# io-board-e-6-renumbered.net
KiCad netlist of a schematic drawn in EAGLE
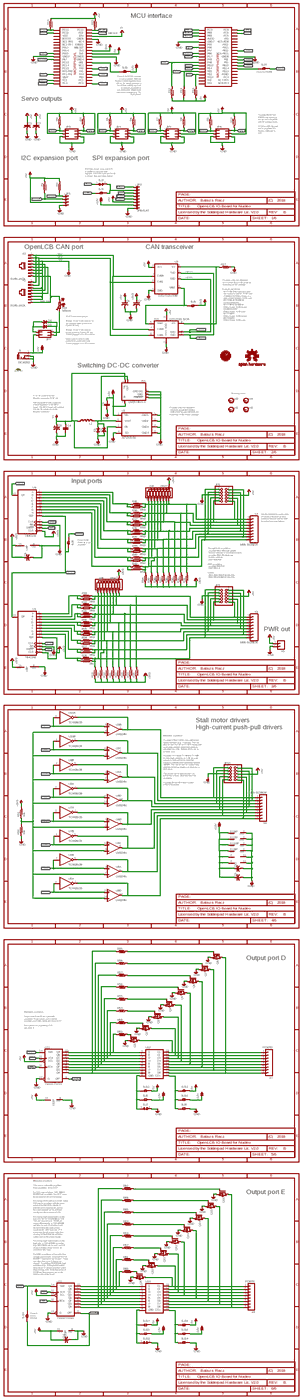
[diagram p0: schematic, sheet 1, overview]
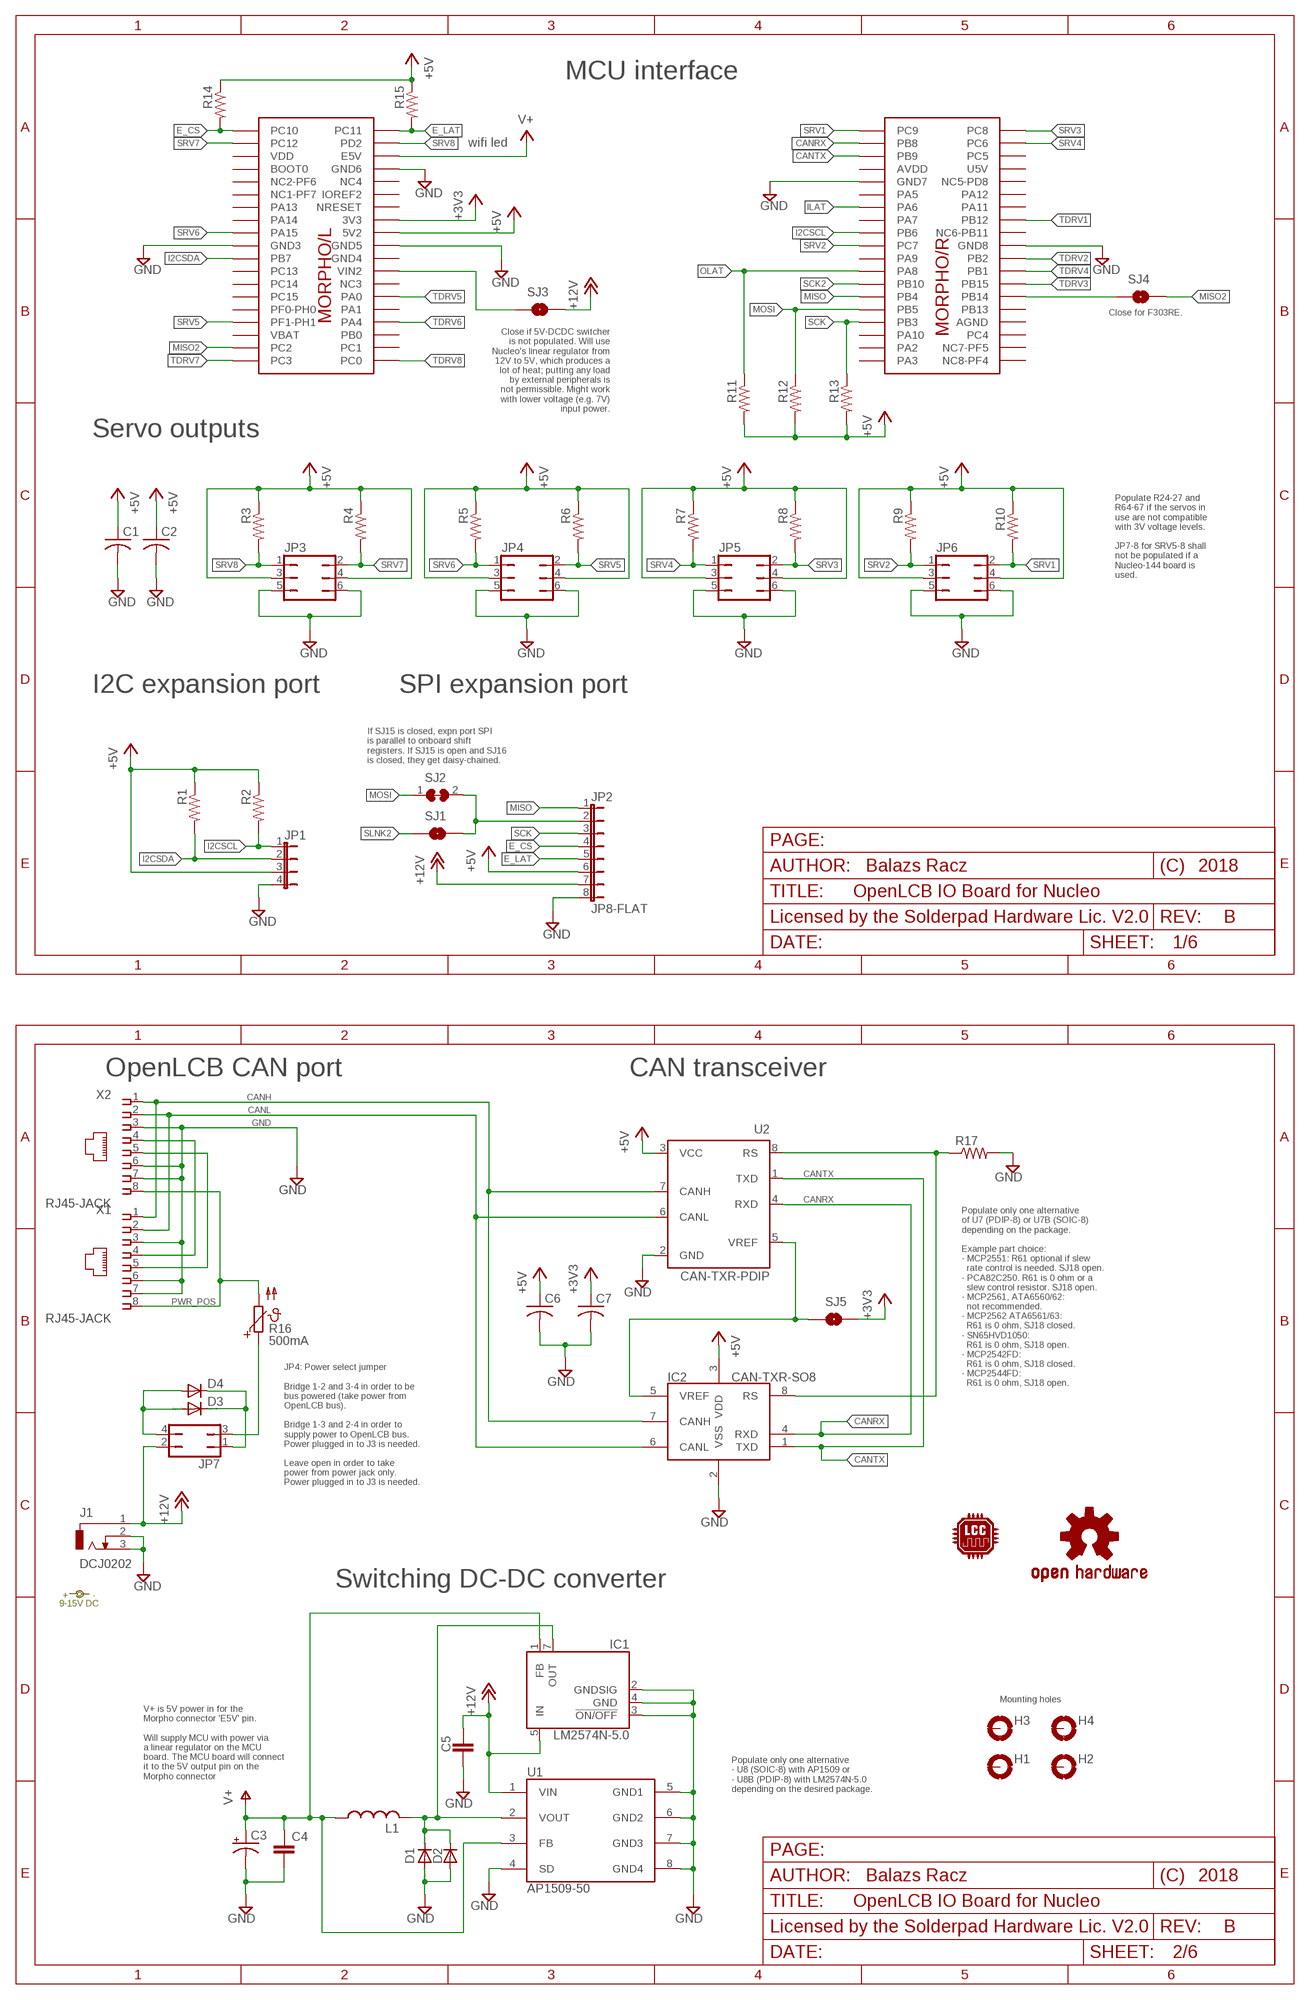
[diagram p1: schematic, sheet 1, part 1 of 4]
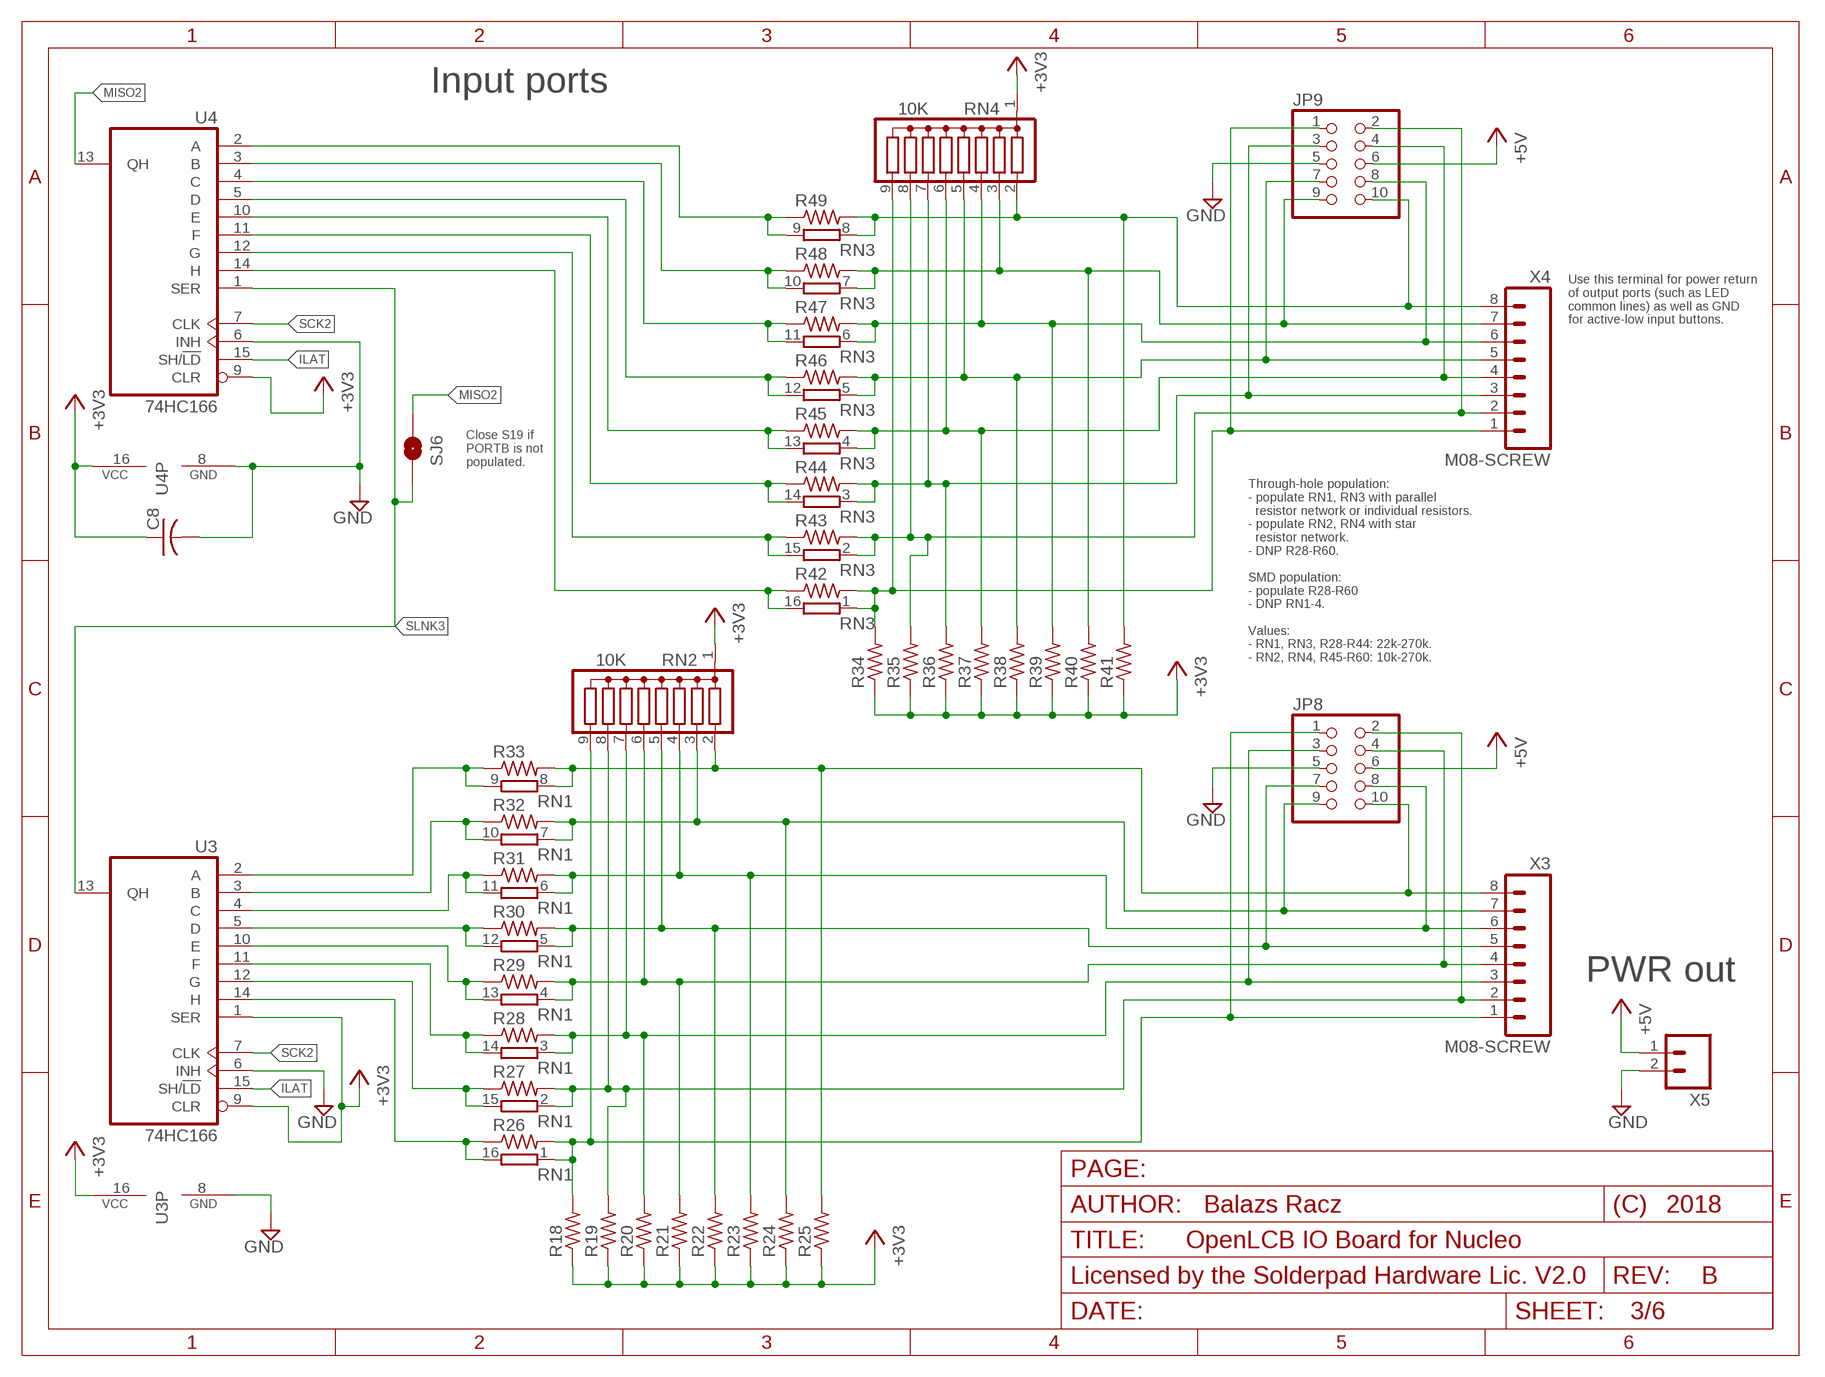
[diagram p2: schematic, sheet 1, part 2 of 4]
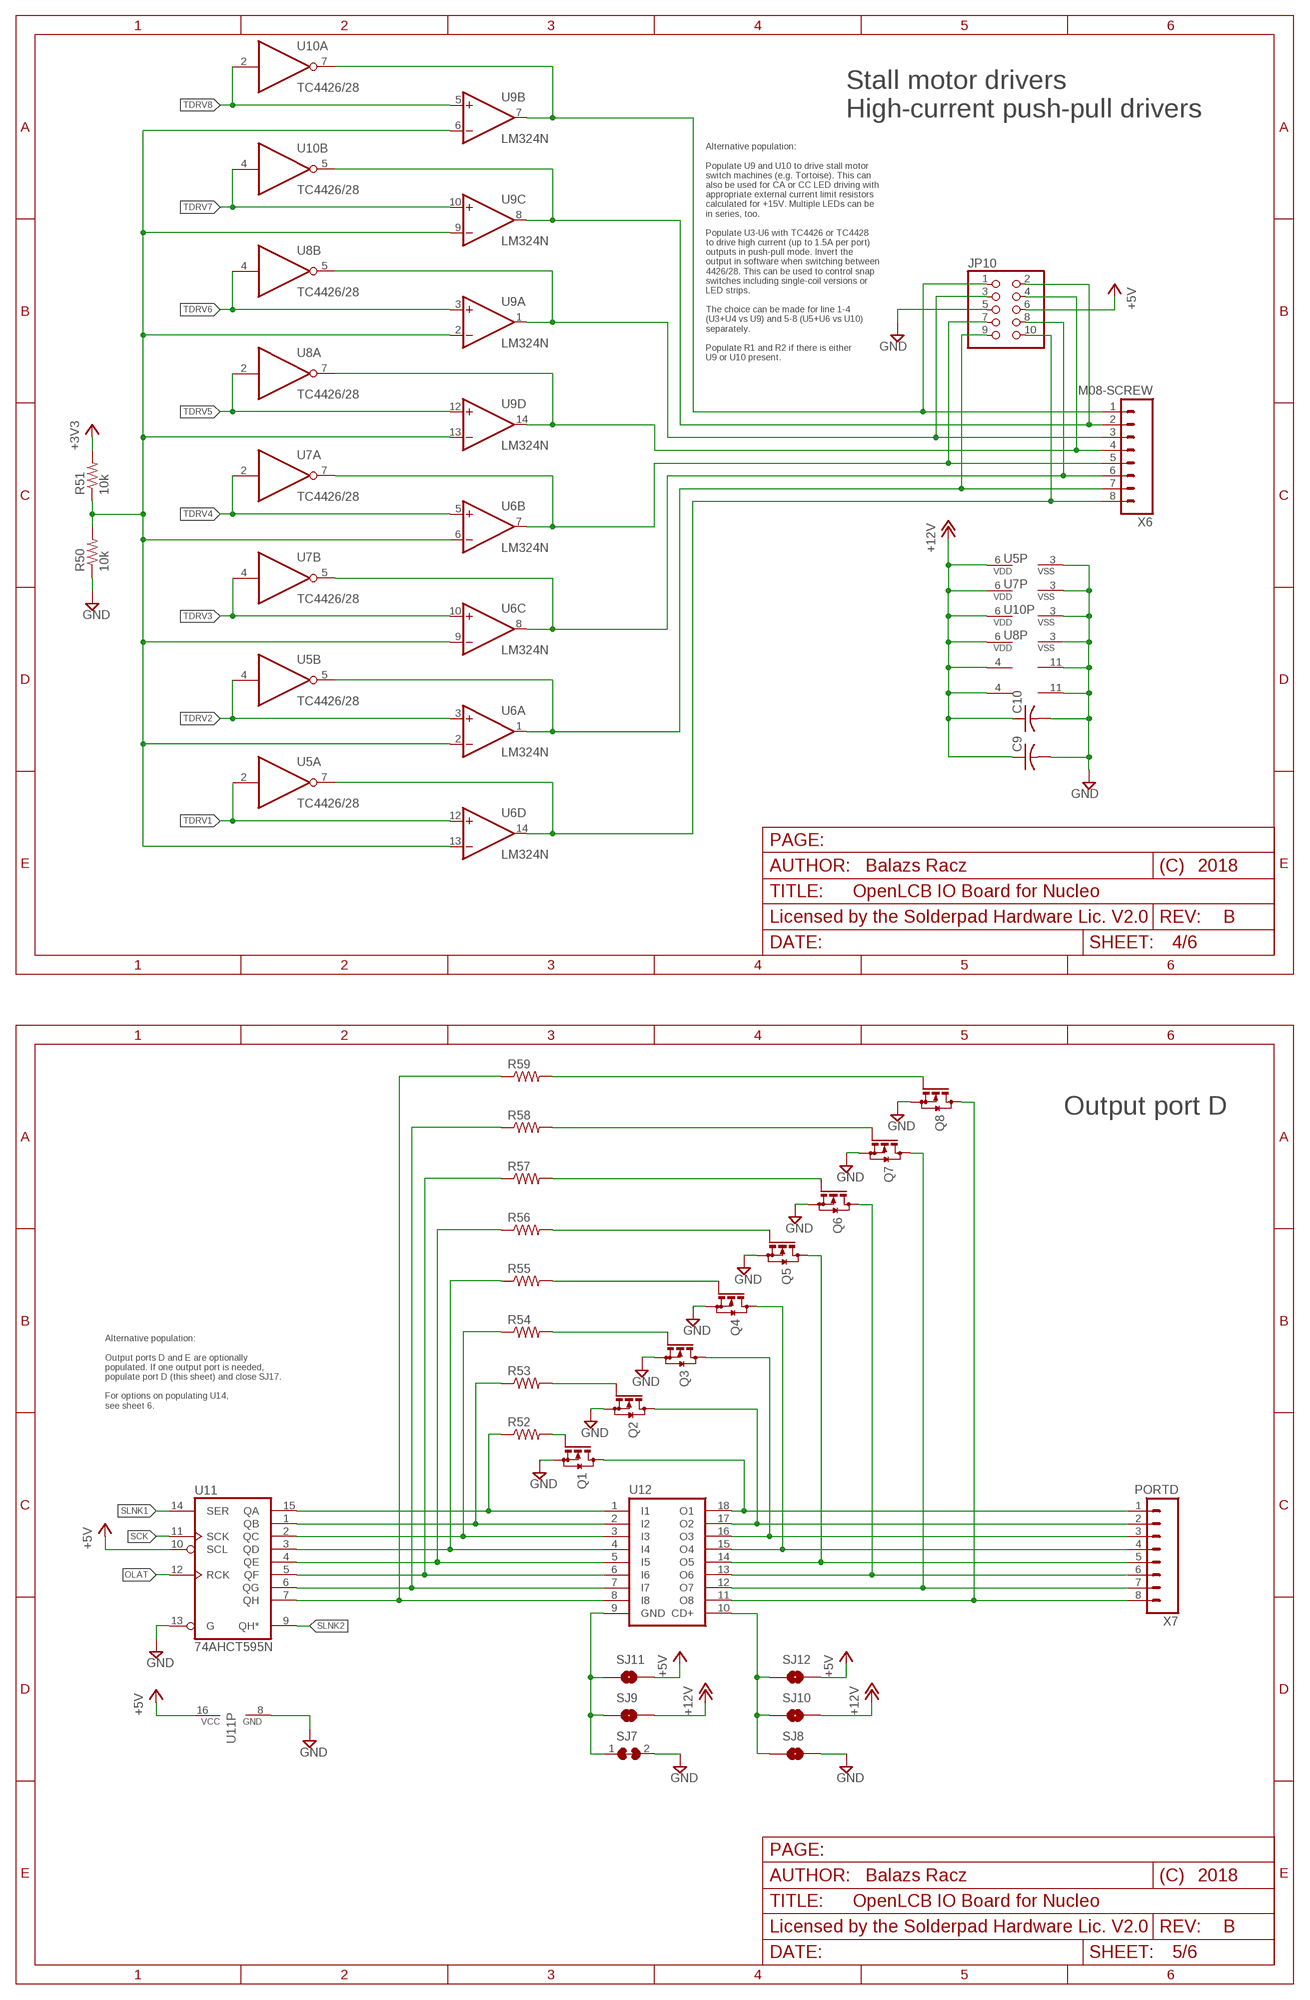
[diagram p3: schematic, sheet 1, part 3 of 4]
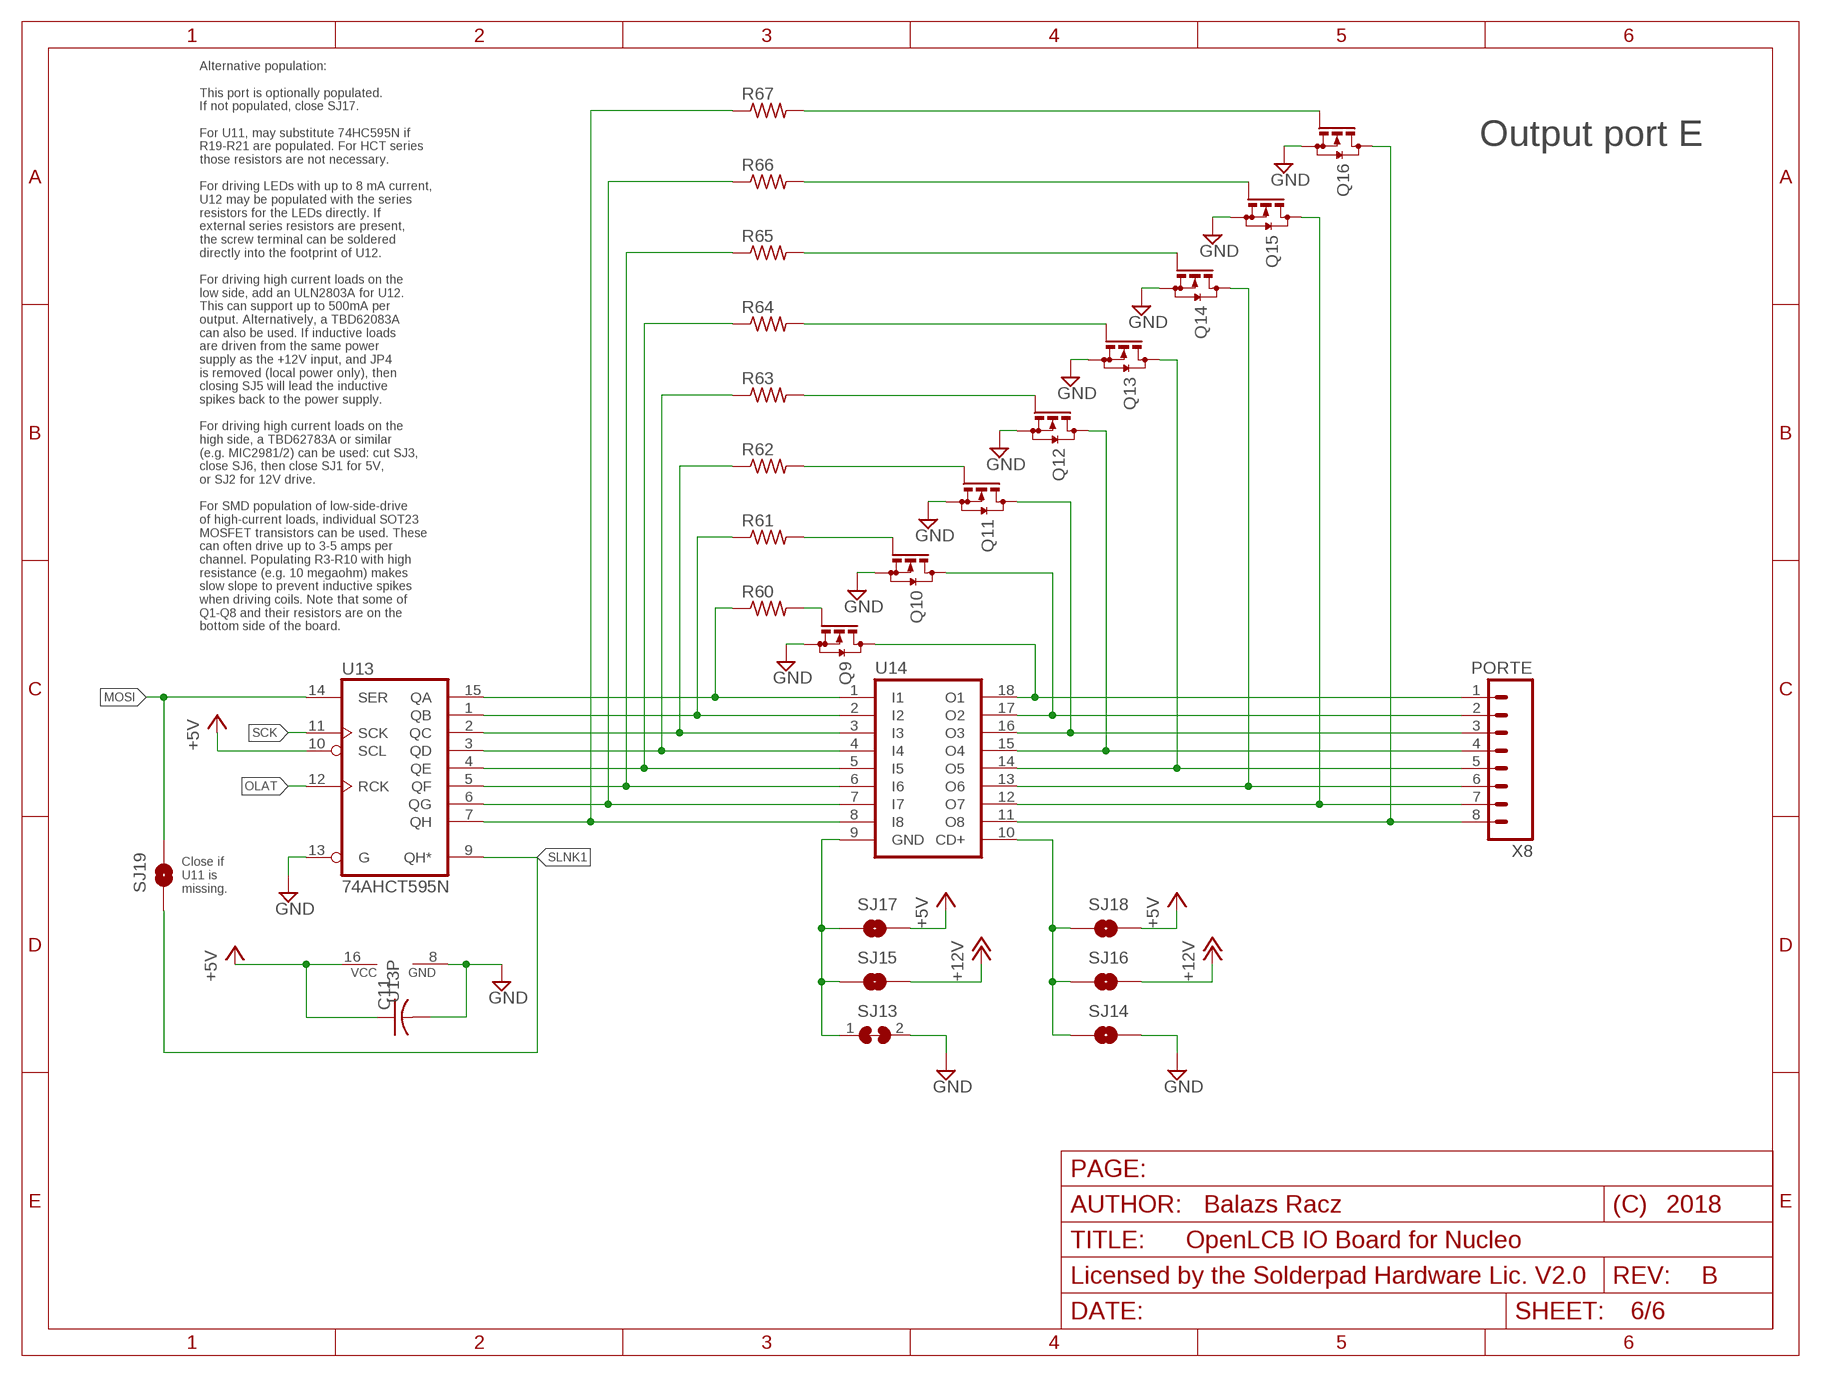
[diagram p4: schematic, sheet 1, part 4 of 4]

(export (version "E")
  (design (tool "Eeschema 10.0.6"))
  (components
    (comp (ref "C1")
      (value "C-USC1206")
      (footprint "eagle-import:C1206")
      (libsource (lib "eagle-import") (part "C-USC1206"))
    )
    (comp (ref "C2")
      (value "C-USC1206")
      (footprint "eagle-import:C1206")
      (libsource (lib "eagle-import") (part "C-USC1206"))
    )
    (comp (ref "C3")
      (value "CPOL-USE2.5-5")
      (footprint "eagle-import:E2,5-5")
      (libsource (lib "eagle-import") (part "CPOL-USE2.5-5"))
    )
    (comp (ref "C4")
      (value "C-EUC1206")
      (footprint "eagle-import:C1206")
      (libsource (lib "eagle-import") (part "C-EUC1206"))
    )
    (comp (ref "C5")
      (value "C-EUC1206")
      (footprint "eagle-import:C1206")
      (libsource (lib "eagle-import") (part "C-EUC1206"))
    )
    (comp (ref "C6")
      (value "C-USC0805")
      (footprint "eagle-import:C0805")
      (libsource (lib "eagle-import") (part "C-USC0805"))
    )
    (comp (ref "C7")
      (value "C-USC0805")
      (footprint "eagle-import:C0805")
      (libsource (lib "eagle-import") (part "C-USC0805"))
    )
    (comp (ref "C8")
      (value "C-USC0805")
      (footprint "eagle-import:C0805")
      (libsource (lib "eagle-import") (part "C-USC0805"))
    )
    (comp (ref "C9")
      (value "C-USC1206")
      (footprint "eagle-import:C1206")
      (libsource (lib "eagle-import") (part "C-USC1206"))
    )
    (comp (ref "C10")
      (value "C-USC1206")
      (footprint "eagle-import:C1206")
      (libsource (lib "eagle-import") (part "C-USC1206"))
    )
    (comp (ref "C11")
      (value "C-USC0805")
      (footprint "eagle-import:C0805")
      (libsource (lib "eagle-import") (part "C-USC0805"))
    )
    (comp (ref "D1")
      (value "DIODE-DO41-7.6")
      (footprint "eagle-import:DO41-7.6")
      (libsource (lib "eagle-import") (part "DIODE-DO41-7.6"))
    )
    (comp (ref "D2")
      (value "DIODEDO-214AA-NODOC")
      (footprint "eagle-import:DO214AA-NODOC")
      (libsource (lib "eagle-import") (part "DIODEDO-214AA-NODOC"))
    )
    (comp (ref "D3")
      (value "DIODE-DO41-7.6")
      (footprint "eagle-import:DO41-7.6")
      (libsource (lib "eagle-import") (part "DIODE-DO41-7.6"))
    )
    (comp (ref "D4")
      (value "DIODEDO-214AA-NODOC")
      (footprint "eagle-import:DO214AA-NODOC")
      (libsource (lib "eagle-import") (part "DIODEDO-214AA-NODOC"))
    )
    (comp (ref "G1")
      (value "NUCLEO_64_GENERIC")
      (footprint "eagle-import:NUCLEO_BRD_BASE64")
      (libsource (lib "eagle-import") (part "NUCLEO_64_GENERIC"))
    )
    (comp (ref "H1")
      (value "MOUNT-PAD-ROUND3.3")
      (footprint "eagle-import:3,3-PAD")
      (libsource (lib "eagle-import") (part "MOUNT-PAD-ROUND3.3"))
    )
    (comp (ref "H2")
      (value "MOUNT-PAD-ROUND3.3")
      (footprint "eagle-import:3,3-PAD")
      (libsource (lib "eagle-import") (part "MOUNT-PAD-ROUND3.3"))
    )
    (comp (ref "H3")
      (value "MOUNT-PAD-ROUND3.3")
      (footprint "eagle-import:3,3-PAD")
      (libsource (lib "eagle-import") (part "MOUNT-PAD-ROUND3.3"))
    )
    (comp (ref "H4")
      (value "MOUNT-PAD-ROUND3.3")
      (footprint "eagle-import:3,3-PAD")
      (libsource (lib "eagle-import") (part "MOUNT-PAD-ROUND3.3"))
    )
    (comp (ref "IC1")
      (value "LM2574N-5.0")
      (footprint "eagle-import:DIL08")
      (libsource (lib "eagle-import") (part "LM2574?-N5.0"))
    )
    (comp (ref "IC2")
      (value "CAN-TXR-SO8")
      (footprint "eagle-import:SO-08")
      (libsource (lib "eagle-import") (part "MCP2551-SN"))
    )
    (comp (ref "J1")
      (value "DCJ0202")
      (footprint "eagle-import:DCJ0202")
      (libsource (lib "eagle-import") (part "DCJ0202"))
    )
    (comp (ref "JP1")
      (value "JP4-FLAT")
      (footprint "eagle-import:JP4F")
      (libsource (lib "eagle-import") (part "JP4-FLAT"))
    )
    (comp (ref "JP2")
      (value "JP8-FLAT")
      (footprint "eagle-import:JP8F")
      (libsource (lib "eagle-import") (part "JP8-FLAT"))
    )
    (comp (ref "JP3")
      (value "JP3Q")
      (footprint "eagle-import:JP3Q")
      (libsource (lib "eagle-import") (part "JP3Q"))
    )
    (comp (ref "JP4")
      (value "JP3Q")
      (footprint "eagle-import:JP3Q")
      (libsource (lib "eagle-import") (part "JP3Q"))
    )
    (comp (ref "JP5")
      (value "JP3Q")
      (footprint "eagle-import:JP3Q")
      (libsource (lib "eagle-import") (part "JP3Q"))
    )
    (comp (ref "JP6")
      (value "JP3Q")
      (footprint "eagle-import:JP3Q")
      (libsource (lib "eagle-import") (part "JP3Q"))
    )
    (comp (ref "JP7")
      (value "JP2Q")
      (footprint "eagle-import:JP2Q")
      (libsource (lib "eagle-import") (part "JP2Q"))
    )
    (comp (ref "JP8")
      (value "PINHD-2X5CN")
      (footprint "eagle-import:CON10M")
      (libsource (lib "eagle-import") (part "PINHD-2X5CN"))
    )
    (comp (ref "JP9")
      (value "PINHD-2X5CN")
      (footprint "eagle-import:CON10M")
      (libsource (lib "eagle-import") (part "PINHD-2X5CN"))
    )
    (comp (ref "JP10")
      (value "PINHD-2X5CN")
      (footprint "eagle-import:CON10M")
      (libsource (lib "eagle-import") (part "PINHD-2X5CN"))
    )
    (comp (ref "L1")
      (value "L-US")
      (footprint "eagle-import:L5-8,5")
      (libsource (lib "eagle-import") (part "L-US"))
    )
    (comp (ref "LG1")
      (value "LCC_LOGO")
      (footprint "eagle-import:LCC_LOGO")
      (libsource (lib "eagle-import") (part "LCC_LOGO"))
    )
    (comp (ref "LOGO1")
      (value "DOC-OSHW-LOGOM")
      (footprint "eagle-import:OSHW-LOGO-M")
      (libsource (lib "eagle-import") (part "DOC-OSHW-LOGOM"))
    )
    (comp (ref "P1")
      (value "9-15V DC")
      (footprint "eagle-import:POWER_USAGE")
      (libsource (lib "eagle-import") (part "DOC-POWER_LABEL"))
    )
    (comp (ref "Q1")
      (value "BSS123")
      (footprint "eagle-import:SOT23")
      (libsource (lib "eagle-import") (part "BSS123"))
    )
    (comp (ref "Q2")
      (value "BSS123")
      (footprint "eagle-import:SOT23")
      (libsource (lib "eagle-import") (part "BSS123"))
    )
    (comp (ref "Q3")
      (value "BSS123")
      (footprint "eagle-import:SOT23")
      (libsource (lib "eagle-import") (part "BSS123"))
    )
    (comp (ref "Q4")
      (value "BSS123")
      (footprint "eagle-import:SOT23")
      (libsource (lib "eagle-import") (part "BSS123"))
    )
    (comp (ref "Q5")
      (value "BSS123")
      (footprint "eagle-import:SOT23")
      (libsource (lib "eagle-import") (part "BSS123"))
    )
    (comp (ref "Q6")
      (value "BSS123")
      (footprint "eagle-import:SOT23")
      (libsource (lib "eagle-import") (part "BSS123"))
    )
    (comp (ref "Q7")
      (value "BSS123")
      (footprint "eagle-import:SOT23")
      (libsource (lib "eagle-import") (part "BSS123"))
    )
    (comp (ref "Q8")
      (value "BSS123")
      (footprint "eagle-import:SOT23")
      (libsource (lib "eagle-import") (part "BSS123"))
    )
    (comp (ref "Q9")
      (value "BSS123")
      (footprint "eagle-import:SOT23")
      (libsource (lib "eagle-import") (part "BSS123"))
    )
    (comp (ref "Q10")
      (value "BSS123")
      (footprint "eagle-import:SOT23")
      (libsource (lib "eagle-import") (part "BSS123"))
    )
    (comp (ref "Q11")
      (value "BSS123")
      (footprint "eagle-import:SOT23")
      (libsource (lib "eagle-import") (part "BSS123"))
    )
    (comp (ref "Q12")
      (value "BSS123")
      (footprint "eagle-import:SOT23")
      (libsource (lib "eagle-import") (part "BSS123"))
    )
    (comp (ref "Q13")
      (value "BSS123")
      (footprint "eagle-import:SOT23")
      (libsource (lib "eagle-import") (part "BSS123"))
    )
    (comp (ref "Q14")
      (value "BSS123")
      (footprint "eagle-import:SOT23")
      (libsource (lib "eagle-import") (part "BSS123"))
    )
    (comp (ref "Q15")
      (value "BSS123")
      (footprint "eagle-import:SOT23")
      (libsource (lib "eagle-import") (part "BSS123"))
    )
    (comp (ref "Q16")
      (value "BSS123")
      (footprint "eagle-import:SOT23")
      (libsource (lib "eagle-import") (part "BSS123"))
    )
    (comp (ref "R1")
      (value "R-US_R0805")
      (footprint "eagle-import:R0805")
      (libsource (lib "eagle-import") (part "rcl_334_R-US_R0805"))
    )
    (comp (ref "R2")
      (value "R-US_R0805")
      (footprint "eagle-import:R0805")
      (libsource (lib "eagle-import") (part "rcl_334_R-US_R0805"))
    )
    (comp (ref "R3")
      (value "R-US_R0805")
      (footprint "eagle-import:R0805")
      (libsource (lib "eagle-import") (part "rcl_334_R-US_R0805"))
    )
    (comp (ref "R4")
      (value "R-US_R0805")
      (footprint "eagle-import:R0805")
      (libsource (lib "eagle-import") (part "rcl_334_R-US_R0805"))
    )
    (comp (ref "R5")
      (value "R-US_R0805")
      (footprint "eagle-import:R0805")
      (libsource (lib "eagle-import") (part "rcl_334_R-US_R0805"))
    )
    (comp (ref "R6")
      (value "R-US_R0805")
      (footprint "eagle-import:R0805")
      (libsource (lib "eagle-import") (part "rcl_334_R-US_R0805"))
    )
    (comp (ref "R7")
      (value "R-US_R0805")
      (footprint "eagle-import:R0805")
      (libsource (lib "eagle-import") (part "rcl_334_R-US_R0805"))
    )
    (comp (ref "R8")
      (value "R-US_R0805")
      (footprint "eagle-import:R0805")
      (libsource (lib "eagle-import") (part "rcl_334_R-US_R0805"))
    )
    (comp (ref "R9")
      (value "R-US_R0805")
      (footprint "eagle-import:R0805")
      (libsource (lib "eagle-import") (part "rcl_334_R-US_R0805"))
    )
    (comp (ref "R10")
      (value "R-US_R0805")
      (footprint "eagle-import:R0805")
      (libsource (lib "eagle-import") (part "rcl_334_R-US_R0805"))
    )
    (comp (ref "R11")
      (value "R-US_R0805")
      (footprint "eagle-import:R0805")
      (libsource (lib "eagle-import") (part "rcl_334_R-US_R0805"))
    )
    (comp (ref "R12")
      (value "R-US_R0805")
      (footprint "eagle-import:R0805")
      (libsource (lib "eagle-import") (part "rcl_334_R-US_R0805"))
    )
    (comp (ref "R13")
      (value "R-US_R0805")
      (footprint "eagle-import:R0805")
      (libsource (lib "eagle-import") (part "rcl_334_R-US_R0805"))
    )
    (comp (ref "R14")
      (value "R-US_R0805")
      (footprint "eagle-import:R0805")
      (libsource (lib "eagle-import") (part "rcl_334_R-US_R0805"))
    )
    (comp (ref "R15")
      (value "R-US_R0805")
      (footprint "eagle-import:R0805")
      (libsource (lib "eagle-import") (part "rcl_334_R-US_R0805"))
    )
    (comp (ref "R16")
      (value "500mA")
      (footprint "eagle-import:PTC1812")
      (libsource (lib "eagle-import") (part "PTC_1812"))
    )
    (comp (ref "R17")
      (value "R-US_R0805")
      (footprint "eagle-import:R0805")
      (libsource (lib "eagle-import") (part "rcl_334_R-US_R0805"))
    )
    (comp (ref "R18")
      (value "R-US")
      (footprint "eagle-import:R0603")
      (libsource (lib "eagle-import") (part "R-US"))
    )
    (comp (ref "R19")
      (value "R-US")
      (footprint "eagle-import:R0603")
      (libsource (lib "eagle-import") (part "R-US"))
    )
    (comp (ref "R20")
      (value "R-US")
      (footprint "eagle-import:R0603")
      (libsource (lib "eagle-import") (part "R-US"))
    )
    (comp (ref "R21")
      (value "R-US")
      (footprint "eagle-import:R0603")
      (libsource (lib "eagle-import") (part "R-US"))
    )
    (comp (ref "R22")
      (value "R-US")
      (footprint "eagle-import:R0603")
      (libsource (lib "eagle-import") (part "R-US"))
    )
    (comp (ref "R23")
      (value "R-US")
      (footprint "eagle-import:R0603")
      (libsource (lib "eagle-import") (part "R-US"))
    )
    (comp (ref "R24")
      (value "R-US")
      (footprint "eagle-import:R0603")
      (libsource (lib "eagle-import") (part "R-US"))
    )
    (comp (ref "R25")
      (value "R-US")
      (footprint "eagle-import:R0603")
      (libsource (lib "eagle-import") (part "R-US"))
    )
    (comp (ref "R26")
      (value "R-US_R0603")
      (footprint "eagle-import:R0603")
      (libsource (lib "eagle-import") (part "rcl_334_R-US_R0603"))
    )
    (comp (ref "R27")
      (value "R-US_R0603")
      (footprint "eagle-import:R0603")
      (libsource (lib "eagle-import") (part "rcl_334_R-US_R0603"))
    )
    (comp (ref "R28")
      (value "R-US_R0603")
      (footprint "eagle-import:R0603")
      (libsource (lib "eagle-import") (part "rcl_334_R-US_R0603"))
    )
    (comp (ref "R29")
      (value "R-US_R0603")
      (footprint "eagle-import:R0603")
      (libsource (lib "eagle-import") (part "rcl_334_R-US_R0603"))
    )
    (comp (ref "R30")
      (value "R-US_R0603")
      (footprint "eagle-import:R0603")
      (libsource (lib "eagle-import") (part "rcl_334_R-US_R0603"))
    )
    (comp (ref "R31")
      (value "R-US_R0603")
      (footprint "eagle-import:R0603")
      (libsource (lib "eagle-import") (part "rcl_334_R-US_R0603"))
    )
    (comp (ref "R32")
      (value "R-US_R0603")
      (footprint "eagle-import:R0603")
      (libsource (lib "eagle-import") (part "rcl_334_R-US_R0603"))
    )
    (comp (ref "R33")
      (value "R-US_R0603")
      (footprint "eagle-import:R0603")
      (libsource (lib "eagle-import") (part "rcl_334_R-US_R0603"))
    )
    (comp (ref "R34")
      (value "R-US")
      (footprint "eagle-import:R0603")
      (libsource (lib "eagle-import") (part "R-US"))
    )
    (comp (ref "R35")
      (value "R-US")
      (footprint "eagle-import:R0603")
      (libsource (lib "eagle-import") (part "R-US"))
    )
    (comp (ref "R36")
      (value "R-US")
      (footprint "eagle-import:R0603")
      (libsource (lib "eagle-import") (part "R-US"))
    )
    (comp (ref "R37")
      (value "R-US")
      (footprint "eagle-import:R0603")
      (libsource (lib "eagle-import") (part "R-US"))
    )
    (comp (ref "R38")
      (value "R-US")
      (footprint "eagle-import:R0603")
      (libsource (lib "eagle-import") (part "R-US"))
    )
    (comp (ref "R39")
      (value "R-US")
      (footprint "eagle-import:R0603")
      (libsource (lib "eagle-import") (part "R-US"))
    )
    (comp (ref "R40")
      (value "R-US")
      (footprint "eagle-import:R0603")
      (libsource (lib "eagle-import") (part "R-US"))
    )
    (comp (ref "R41")
      (value "R-US")
      (footprint "eagle-import:R0603")
      (libsource (lib "eagle-import") (part "R-US"))
    )
    (comp (ref "R42")
      (value "R-US_R0603")
      (footprint "eagle-import:R0603")
      (libsource (lib "eagle-import") (part "rcl_334_R-US_R0603"))
    )
    (comp (ref "R43")
      (value "R-US_R0603")
      (footprint "eagle-import:R0603")
      (libsource (lib "eagle-import") (part "rcl_334_R-US_R0603"))
    )
    (comp (ref "R44")
      (value "R-US_R0603")
      (footprint "eagle-import:R0603")
      (libsource (lib "eagle-import") (part "rcl_334_R-US_R0603"))
    )
    (comp (ref "R45")
      (value "R-US_R0603")
      (footprint "eagle-import:R0603")
      (libsource (lib "eagle-import") (part "rcl_334_R-US_R0603"))
    )
    (comp (ref "R46")
      (value "R-US_R0603")
      (footprint "eagle-import:R0603")
      (libsource (lib "eagle-import") (part "rcl_334_R-US_R0603"))
    )
    (comp (ref "R47")
      (value "R-US_R0603")
      (footprint "eagle-import:R0603")
      (libsource (lib "eagle-import") (part "rcl_334_R-US_R0603"))
    )
    (comp (ref "R48")
      (value "R-US_R0603")
      (footprint "eagle-import:R0603")
      (libsource (lib "eagle-import") (part "rcl_334_R-US_R0603"))
    )
    (comp (ref "R49")
      (value "R-US_R0603")
      (footprint "eagle-import:R0603")
      (libsource (lib "eagle-import") (part "rcl_334_R-US_R0603"))
    )
    (comp (ref "R50")
      (value "10k")
      (footprint "eagle-import:R0805")
      (libsource (lib "eagle-import") (part "R-US_R0805"))
    )
    (comp (ref "R51")
      (value "10k")
      (footprint "eagle-import:R0805")
      (libsource (lib "eagle-import") (part "R-US_R0805"))
    )
    (comp (ref "R52")
      (value "R-US_R0603")
      (footprint "eagle-import:R0603")
      (libsource (lib "eagle-import") (part "R-US_R0603"))
    )
    (comp (ref "R53")
      (value "R-US_R0603")
      (footprint "eagle-import:R0603")
      (libsource (lib "eagle-import") (part "R-US_R0603"))
    )
    (comp (ref "R54")
      (value "R-US_R0603")
      (footprint "eagle-import:R0603")
      (libsource (lib "eagle-import") (part "R-US_R0603"))
    )
    (comp (ref "R55")
      (value "R-US_R0603")
      (footprint "eagle-import:R0603")
      (libsource (lib "eagle-import") (part "R-US_R0603"))
    )
    (comp (ref "R56")
      (value "R-US_R0603")
      (footprint "eagle-import:R0603")
      (libsource (lib "eagle-import") (part "R-US_R0603"))
    )
    (comp (ref "R57")
      (value "R-US_R0603")
      (footprint "eagle-import:R0603")
      (libsource (lib "eagle-import") (part "R-US_R0603"))
    )
    (comp (ref "R58")
      (value "R-US_R0603")
      (footprint "eagle-import:R0603")
      (libsource (lib "eagle-import") (part "R-US_R0603"))
    )
    (comp (ref "R59")
      (value "R-US_R0603")
      (footprint "eagle-import:R0603")
      (libsource (lib "eagle-import") (part "R-US_R0603"))
    )
    (comp (ref "R60")
      (value "R-US_R0603")
      (footprint "eagle-import:R0603")
      (libsource (lib "eagle-import") (part "R-US_R0603"))
    )
    (comp (ref "R61")
      (value "R-US_R0603")
      (footprint "eagle-import:R0603")
      (libsource (lib "eagle-import") (part "R-US_R0603"))
    )
    (comp (ref "R62")
      (value "R-US_R0603")
      (footprint "eagle-import:R0603")
      (libsource (lib "eagle-import") (part "R-US_R0603"))
    )
    (comp (ref "R63")
      (value "R-US_R0603")
      (footprint "eagle-import:R0603")
      (libsource (lib "eagle-import") (part "R-US_R0603"))
    )
    (comp (ref "R64")
      (value "R-US_R0603")
      (footprint "eagle-import:R0603")
      (libsource (lib "eagle-import") (part "R-US_R0603"))
    )
    (comp (ref "R65")
      (value "R-US_R0603")
      (footprint "eagle-import:R0603")
      (libsource (lib "eagle-import") (part "R-US_R0603"))
    )
    (comp (ref "R66")
      (value "R-US_R0603")
      (footprint "eagle-import:R0603")
      (libsource (lib "eagle-import") (part "R-US_R0603"))
    )
    (comp (ref "R67")
      (value "R-US_R0603")
      (footprint "eagle-import:R0603")
      (libsource (lib "eagle-import") (part "R-US_R0603"))
    )
    (comp (ref "RN1")
      (value "8R-P")
      (footprint "eagle-import:DIL16")
      (libsource (lib "eagle-import") (part "8R-P"))
    )
    (comp (ref "RN2")
      (value "10K")
      (footprint "eagle-import:SIL9")
      (libsource (lib "eagle-import") (part "G08R"))
    )
    (comp (ref "RN3")
      (value "8R-P")
      (footprint "eagle-import:DIL16")
      (libsource (lib "eagle-import") (part "8R-P"))
    )
    (comp (ref "RN4")
      (value "10K")
      (footprint "eagle-import:SIL9")
      (libsource (lib "eagle-import") (part "G08R"))
    )
    (comp (ref "SJ1")
      (value "SJRND2")
      (footprint "eagle-import:SJ_RND2")
      (libsource (lib "eagle-import") (part "SJRND2"))
    )
    (comp (ref "SJ2")
      (value "SJ-C")
      (footprint "eagle-import:SJW-C")
      (libsource (lib "eagle-import") (part "SJ-C"))
    )
    (comp (ref "SJ3")
      (value "SJRND2")
      (footprint "eagle-import:SJ_RND2")
      (libsource (lib "eagle-import") (part "SJRND2"))
    )
    (comp (ref "SJ4")
      (value "SJRND2")
      (footprint "eagle-import:SJ_RND2")
      (libsource (lib "eagle-import") (part "SJRND2"))
    )
    (comp (ref "SJ5")
      (value "SJRND2")
      (footprint "eagle-import:SJ_RND2")
      (libsource (lib "eagle-import") (part "SJRND2"))
    )
    (comp (ref "SJ6")
      (value "SJRND2")
      (footprint "eagle-import:SJ_RND2")
      (libsource (lib "eagle-import") (part "SJRND2"))
    )
    (comp (ref "SJ7")
      (value "SJ-C")
      (footprint "eagle-import:SJW-C")
      (libsource (lib "eagle-import") (part "SJ-C"))
    )
    (comp (ref "SJ8")
      (value "SJRND2")
      (footprint "eagle-import:SJ_RND2")
      (libsource (lib "eagle-import") (part "SJRND2"))
    )
    (comp (ref "SJ9")
      (value "SJRND2")
      (footprint "eagle-import:SJ_RND2")
      (libsource (lib "eagle-import") (part "SJRND2"))
    )
    (comp (ref "SJ10")
      (value "SJRND2")
      (footprint "eagle-import:SJ_RND2")
      (libsource (lib "eagle-import") (part "SJRND2"))
    )
    (comp (ref "SJ11")
      (value "SJRND2")
      (footprint "eagle-import:SJ_RND2")
      (libsource (lib "eagle-import") (part "SJRND2"))
    )
    (comp (ref "SJ12")
      (value "SJRND2")
      (footprint "eagle-import:SJ_RND2")
      (libsource (lib "eagle-import") (part "SJRND2"))
    )
    (comp (ref "SJ13")
      (value "SJ-C")
      (footprint "eagle-import:SJW-C")
      (libsource (lib "eagle-import") (part "SJ-C"))
    )
    (comp (ref "SJ14")
      (value "SJRND2")
      (footprint "eagle-import:SJ_RND2")
      (libsource (lib "eagle-import") (part "SJRND2"))
    )
    (comp (ref "SJ15")
      (value "SJRND2")
      (footprint "eagle-import:SJ_RND2")
      (libsource (lib "eagle-import") (part "SJRND2"))
    )
    (comp (ref "SJ16")
      (value "SJRND2")
      (footprint "eagle-import:SJ_RND2")
      (libsource (lib "eagle-import") (part "SJRND2"))
    )
    (comp (ref "SJ17")
      (value "SJRND2")
      (footprint "eagle-import:SJ_RND2")
      (libsource (lib "eagle-import") (part "SJRND2"))
    )
    (comp (ref "SJ18")
      (value "SJRND2")
      (footprint "eagle-import:SJ_RND2")
      (libsource (lib "eagle-import") (part "SJRND2"))
    )
    (comp (ref "SJ19")
      (value "SJRND2")
      (footprint "eagle-import:SJ_RND2")
      (libsource (lib "eagle-import") (part "SJRND2"))
    )
    (comp (ref "U1")
      (value "AP1509-50")
      (footprint "eagle-import:SO-08")
      (libsource (lib "eagle-import") (part "AP1509"))
    )
    (comp (ref "U2")
      (value "CAN-TXR-PDIP")
      (footprint "eagle-import:DIL08")
      (libsource (lib "eagle-import") (part "PCA82C250"))
    )
    (comp (ref "U3")
      (value "74HC166")
      (footprint "eagle-import:DIL16")
      (libsource (lib "eagle-import") (part "74166N"))
    )
    (comp (ref "U4")
      (value "74HC166")
      (footprint "eagle-import:DIL16")
      (libsource (lib "eagle-import") (part "74166N"))
    )
    (comp (ref "U5")
      (value "TC4426/28")
      (footprint "eagle-import:DIL08-LONG")
      (libsource (lib "eagle-import") (part "TC4426APDIP"))
    )
    (comp (ref "U6")
      (value "LM324N")
      (footprint "eagle-import:DIL14")
      (libsource (lib "eagle-import") (part "LM324N"))
    )
    (comp (ref "U7")
      (value "TC4426/28")
      (footprint "eagle-import:DIL08-LONG")
      (libsource (lib "eagle-import") (part "TC4426APDIP"))
    )
    (comp (ref "U8")
      (value "TC4426/28")
      (footprint "eagle-import:DIL08-LONG")
      (libsource (lib "eagle-import") (part "TC4426APDIP"))
    )
    (comp (ref "U9")
      (value "LM324N")
      (footprint "eagle-import:DIL14")
      (libsource (lib "eagle-import") (part "LM324N"))
    )
    (comp (ref "U10")
      (value "TC4426/28")
      (footprint "eagle-import:DIL08-LONG")
      (libsource (lib "eagle-import") (part "TC4426APDIP"))
    )
    (comp (ref "U11")
      (value "74AHCT595N")
      (footprint "eagle-import:DIL16")
      (libsource (lib "eagle-import") (part "74595NHCT"))
    )
    (comp (ref "U12")
      (value "ULN2803A")
      (footprint "eagle-import:DIL18-THIN")
      (libsource (lib "eagle-import") (part "ULN2803A"))
    )
    (comp (ref "U13")
      (value "74AHCT595N")
      (footprint "eagle-import:DIL16")
      (libsource (lib "eagle-import") (part "74595NHCT"))
    )
    (comp (ref "U14")
      (value "ULN2803A")
      (footprint "eagle-import:DIL18-THIN")
      (libsource (lib "eagle-import") (part "ULN2803A"))
    )
    (comp (ref "X1")
      (value "RJ45-JACK")
      (footprint "eagle-import:RJ45-PULSE-E5J88")
      (libsource (lib "eagle-import") (part "RJ45-JACKRJ45-PULSE-E5J00"))
    )
    (comp (ref "X2")
      (value "RJ45-JACK")
      (footprint "eagle-import:RJ45-PULSE-E5J88")
      (libsource (lib "eagle-import") (part "RJ45-JACKRJ45-PULSE-E5J00"))
    )
    (comp (ref "X3")
      (value "M08-SCREW")
      (footprint "eagle-import:1X08_TERMINAL")
      (libsource (lib "eagle-import") (part "M08-SCREW"))
    )
    (comp (ref "X4")
      (value "M08-SCREW")
      (footprint "eagle-import:1X08_TERMINAL")
      (libsource (lib "eagle-import") (part "M08-SCREW"))
    )
    (comp (ref "X5")
      (value "CONNECTOR-M023.5MM-LOCK")
      (footprint "eagle-import:SCREWTERMINAL-3.5MM-2_LOCK")
      (libsource (lib "eagle-import") (part "CONNECTOR-M023.5MM-LOCK"))
    )
    (comp (ref "X6")
      (value "M08-SCREW")
      (footprint "eagle-import:1X08_TERMINAL")
      (libsource (lib "eagle-import") (part "M08-SCREW"))
    )
    (comp (ref "X7")
      (value "PORTD")
      (footprint "eagle-import:1X08_TERMINAL")
      (libsource (lib "eagle-import") (part "M08-SCREW"))
    )
    (comp (ref "X8")
      (value "PORTE")
      (footprint "eagle-import:1X08_TERMINAL")
      (libsource (lib "eagle-import") (part "M08-SCREW"))
    )
  )
  (nets
    (net (code "1") (name "+3V3") (class "Default")
      (node (ref "C7") (pin "1") (pinfunction "1_1") (pintype "passive"))
      (node (ref "C8") (pin "1") (pinfunction "1_1") (pintype "passive"))
      (node (ref "G1") (pin "3V3") (pinfunction "3V3_3V3") (pintype "power_in"))
      (node (ref "R18") (pin "1") (pinfunction "1_1") (pintype "passive"))
      (node (ref "R19") (pin "1") (pinfunction "1_1") (pintype "passive"))
      (node (ref "R20") (pin "1") (pinfunction "1_1") (pintype "passive"))
      (node (ref "R21") (pin "1") (pinfunction "1_1") (pintype "passive"))
      (node (ref "R22") (pin "1") (pinfunction "1_1") (pintype "passive"))
      (node (ref "R23") (pin "1") (pinfunction "1_1") (pintype "passive"))
      (node (ref "R24") (pin "1") (pinfunction "1_1") (pintype "passive"))
      (node (ref "R25") (pin "1") (pinfunction "1_1") (pintype "passive"))
      (node (ref "R34") (pin "1") (pinfunction "1_1") (pintype "passive"))
      (node (ref "R35") (pin "1") (pinfunction "1_1") (pintype "passive"))
      (node (ref "R36") (pin "1") (pinfunction "1_1") (pintype "passive"))
      (node (ref "R37") (pin "1") (pinfunction "1_1") (pintype "passive"))
      (node (ref "R38") (pin "1") (pinfunction "1_1") (pintype "passive"))
      (node (ref "R39") (pin "1") (pinfunction "1_1") (pintype "passive"))
      (node (ref "R40") (pin "1") (pinfunction "1_1") (pintype "passive"))
      (node (ref "R41") (pin "1") (pinfunction "1_1") (pintype "passive"))
      (node (ref "R51") (pin "2") (pinfunction "2_2") (pintype "passive"))
      (node (ref "RN2") (pin "1") (pinfunction "1_1") (pintype "passive"))
      (node (ref "RN4") (pin "1") (pinfunction "1_1") (pintype "passive"))
      (node (ref "SJ5") (pin "P$1") (pinfunction "1_P$1") (pintype "passive"))
      (node (ref "U3") (pin "1") (pinfunction "SER_1") (pintype "input"))
      (node (ref "U3") (pin "16") (pinfunction "VCC_16") (pintype "power_in"))
      (node (ref "U3") (pin "9") (pinfunction "CLR_9") (pintype "input"))
      (node (ref "U4") (pin "16") (pinfunction "VCC_16") (pintype "power_in"))
      (node (ref "U4") (pin "9") (pinfunction "CLR_9") (pintype "input"))
    )
    (net (code "2") (name "+5V") (class "Default")
      (node (ref "C1") (pin "1") (pinfunction "1_1") (pintype "passive"))
      (node (ref "C11") (pin "1") (pinfunction "1_1") (pintype "passive"))
      (node (ref "C2") (pin "1") (pinfunction "1_1") (pintype "passive"))
      (node (ref "C6") (pin "1") (pinfunction "1_1") (pintype "passive"))
      (node (ref "G1") (pin "5V2") (pinfunction "5V2_5V2") (pintype "power_in"))
      (node (ref "IC2") (pin "3") (pinfunction "VDD_3") (pintype "power_in"))
      (node (ref "JP1") (pin "3") (pinfunction "3_3") (pintype "passive"))
      (node (ref "JP10") (pin "6") (pinfunction "6_6") (pintype "passive"))
      (node (ref "JP2") (pin "6") (pinfunction "6_6") (pintype "passive"))
      (node (ref "JP3") (pin "3") (pinfunction "3_3") (pintype "passive"))
      (node (ref "JP3") (pin "4") (pinfunction "4_4") (pintype "passive"))
      (node (ref "JP4") (pin "3") (pinfunction "3_3") (pintype "passive"))
      (node (ref "JP4") (pin "4") (pinfunction "4_4") (pintype "passive"))
      (node (ref "JP5") (pin "3") (pinfunction "3_3") (pintype "passive"))
      (node (ref "JP5") (pin "4") (pinfunction "4_4") (pintype "passive"))
      (node (ref "JP6") (pin "3") (pinfunction "3_3") (pintype "passive"))
      (node (ref "JP6") (pin "4") (pinfunction "4_4") (pintype "passive"))
      (node (ref "JP8") (pin "6") (pinfunction "6_6") (pintype "passive"))
      (node (ref "JP9") (pin "6") (pinfunction "6_6") (pintype "passive"))
      (node (ref "R1") (pin "1") (pinfunction "1_1") (pintype "passive"))
      (node (ref "R10") (pin "1") (pinfunction "1_1") (pintype "passive"))
      (node (ref "R11") (pin "2") (pinfunction "2_2") (pintype "passive"))
      (node (ref "R12") (pin "2") (pinfunction "2_2") (pintype "passive"))
      (node (ref "R13") (pin "2") (pinfunction "2_2") (pintype "passive"))
      (node (ref "R14") (pin "1") (pinfunction "1_1") (pintype "passive"))
      (node (ref "R15") (pin "1") (pinfunction "1_1") (pintype "passive"))
      (node (ref "R2") (pin "1") (pinfunction "1_1") (pintype "passive"))
      (node (ref "R3") (pin "1") (pinfunction "1_1") (pintype "passive"))
      (node (ref "R4") (pin "1") (pinfunction "1_1") (pintype "passive"))
      (node (ref "R5") (pin "1") (pinfunction "1_1") (pintype "passive"))
      (node (ref "R6") (pin "1") (pinfunction "1_1") (pintype "passive"))
      (node (ref "R7") (pin "1") (pinfunction "1_1") (pintype "passive"))
      (node (ref "R8") (pin "1") (pinfunction "1_1") (pintype "passive"))
      (node (ref "R9") (pin "1") (pinfunction "1_1") (pintype "passive"))
      (node (ref "SJ11") (pin "P$2") (pinfunction "2_P$2") (pintype "passive"))
      (node (ref "SJ12") (pin "P$2") (pinfunction "2_P$2") (pintype "passive"))
      (node (ref "SJ17") (pin "P$2") (pinfunction "2_P$2") (pintype "passive"))
      (node (ref "SJ18") (pin "P$2") (pinfunction "2_P$2") (pintype "passive"))
      (node (ref "U11") (pin "10") (pinfunction "SCL_10") (pintype "input"))
      (node (ref "U11") (pin "16") (pinfunction "VCC_16") (pintype "power_in"))
      (node (ref "U13") (pin "10") (pinfunction "SCL_10") (pintype "input"))
      (node (ref "U13") (pin "16") (pinfunction "VCC_16") (pintype "power_in"))
      (node (ref "U2") (pin "3") (pinfunction "VCC_3") (pintype "power_in"))
      (node (ref "X5") (pin "1") (pinfunction "1_1") (pintype "passive"))
    )
    (net (code "3") (name "+12V") (class "Default")
      (node (ref "C10") (pin "1") (pinfunction "1_1") (pintype "passive"))
      (node (ref "C5") (pin "1") (pinfunction "1_1") (pintype "passive"))
      (node (ref "C9") (pin "1") (pinfunction "1_1") (pintype "passive"))
      (node (ref "IC1") (pin "5") (pinfunction "IN_5") (pintype "input"))
      (node (ref "J1") (pin "1") (pinfunction "1_1") (pintype "passive"))
      (node (ref "JP2") (pin "7") (pinfunction "7_7") (pintype "passive"))
      (node (ref "JP7") (pin "2") (pinfunction "2_2") (pintype "passive"))
      (node (ref "SJ10") (pin "P$2") (pinfunction "2_P$2") (pintype "passive"))
      (node (ref "SJ15") (pin "P$2") (pinfunction "2_P$2") (pintype "passive"))
      (node (ref "SJ16") (pin "P$2") (pinfunction "2_P$2") (pintype "passive"))
      (node (ref "SJ3") (pin "P$2") (pinfunction "2_P$2") (pintype "passive"))
      (node (ref "SJ9") (pin "P$2") (pinfunction "2_P$2") (pintype "passive"))
      (node (ref "U1") (pin "1") (pinfunction "VIN_1") (pintype "bidirectional"))
      (node (ref "U10") (pin "6") (pinfunction "VDD_6") (pintype "power_in"))
      (node (ref "U5") (pin "6") (pinfunction "VDD_6") (pintype "power_in"))
      (node (ref "U6") (pin "4") (pinfunction "V+_4") (pintype "power_in"))
      (node (ref "U7") (pin "6") (pinfunction "VDD_6") (pintype "power_in"))
      (node (ref "U8") (pin "6") (pinfunction "VDD_6") (pintype "power_in"))
      (node (ref "U9") (pin "4") (pinfunction "V+_4") (pintype "power_in"))
    )
    (net (code "4") (name "/AGND") (class "Default")
      (node (ref "G1") (pin "AGND") (pinfunction "AGND_AGND") (pintype "power_in"))
    )
    (net (code "5") (name "/AVDD") (class "Default")
      (node (ref "G1") (pin "AVDD") (pinfunction "AVDD_AVDD") (pintype "power_in"))
    )
    (net (code "6") (name "/CANH") (class "Default")
      (node (ref "IC2") (pin "7") (pinfunction "CANH_7") (pintype "bidirectional"))
      (node (ref "U2") (pin "7") (pinfunction "CANH_7") (pintype "bidirectional"))
      (node (ref "X1") (pin "1") (pinfunction "1_1") (pintype "passive"))
      (node (ref "X2") (pin "1") (pinfunction "1_1") (pintype "passive"))
    )
    (net (code "7") (name "/CANL") (class "Default")
      (node (ref "IC2") (pin "6") (pinfunction "CANL_6") (pintype "bidirectional"))
      (node (ref "U2") (pin "6") (pinfunction "CANL_6") (pintype "bidirectional"))
      (node (ref "X1") (pin "2") (pinfunction "2_2") (pintype "passive"))
      (node (ref "X2") (pin "2") (pinfunction "2_2") (pintype "passive"))
    )
    (net (code "8") (name "/GND4") (class "Default")
      (node (ref "G1") (pin "GND4") (pinfunction "GND4_GND4") (pintype "power_in"))
    )
    (net (code "9") (name "/PWR_POS") (class "Default")
      (node (ref "R16") (pin "2") (pinfunction "2_2") (pintype "passive"))
      (node (ref "X1") (pin "8") (pinfunction "8_8") (pintype "passive"))
      (node (ref "X2") (pin "8") (pinfunction "8_8") (pintype "passive"))
    )
    (net (code "10") (name "/U5V") (class "Default")
      (node (ref "G1") (pin "U5V") (pinfunction "U5V_U5V") (pintype "power_in"))
    )
    (net (code "11") (name "/VBAT") (class "Default")
      (node (ref "G1") (pin "VBAT") (pinfunction "VBAT_VBAT") (pintype "power_in"))
    )
    (net (code "12") (name "/VDD") (class "Default")
      (node (ref "G1") (pin "VDD") (pinfunction "VDD_VDD") (pintype "power_in"))
    )
    (net (code "13") (name "CANRX") (class "Default")
      (node (ref "G1") (pin "PB8") (pinfunction "PB8_PB8") (pintype "bidirectional"))
      (node (ref "IC2") (pin "4") (pinfunction "RXD_4") (pintype "bidirectional"))
      (node (ref "U2") (pin "4") (pinfunction "RXD_4") (pintype "output"))
    )
    (net (code "14") (name "CANTX") (class "Default")
      (node (ref "G1") (pin "PB9") (pinfunction "PB9_PB9") (pintype "bidirectional"))
      (node (ref "IC2") (pin "1") (pinfunction "TXD_1") (pintype "bidirectional"))
      (node (ref "U2") (pin "1") (pinfunction "TXD_1") (pintype "input"))
    )
    (net (code "15") (name "E_CS") (class "Default")
      (node (ref "G1") (pin "PC10") (pinfunction "PC10_PC10") (pintype "bidirectional"))
      (node (ref "JP2") (pin "4") (pinfunction "4_4") (pintype "passive"))
      (node (ref "R14") (pin "2") (pinfunction "2_2") (pintype "passive"))
    )
    (net (code "16") (name "E_LAT") (class "Default")
      (node (ref "G1") (pin "PC11") (pinfunction "PC11_PC11") (pintype "bidirectional"))
      (node (ref "JP2") (pin "5") (pinfunction "5_5") (pintype "passive"))
      (node (ref "R15") (pin "2") (pinfunction "2_2") (pintype "passive"))
    )
    (net (code "17") (name "GND") (class "Default")
      (node (ref "C1") (pin "2") (pinfunction "2_2") (pintype "passive"))
      (node (ref "C10") (pin "2") (pinfunction "2_2") (pintype "passive"))
      (node (ref "C11") (pin "2") (pinfunction "2_2") (pintype "passive"))
      (node (ref "C2") (pin "2") (pinfunction "2_2") (pintype "passive"))
      (node (ref "C3") (pin "-") (pinfunction "-_-") (pintype "passive"))
      (node (ref "C4") (pin "2") (pinfunction "2_2") (pintype "passive"))
      (node (ref "C5") (pin "2") (pinfunction "2_2") (pintype "passive"))
      (node (ref "C6") (pin "2") (pinfunction "2_2") (pintype "passive"))
      (node (ref "C7") (pin "2") (pinfunction "2_2") (pintype "passive"))
      (node (ref "C8") (pin "2") (pinfunction "2_2") (pintype "passive"))
      (node (ref "C9") (pin "2") (pinfunction "2_2") (pintype "passive"))
      (node (ref "D1") (pin "A") (pinfunction "A_A") (pintype "passive"))
      (node (ref "D2") (pin "A") (pinfunction "A_A") (pintype "passive"))
      (node (ref "G1") (pin "GND3") (pinfunction "GND3_GND3") (pintype "power_in"))
      (node (ref "G1") (pin "GND5") (pinfunction "GND5_GND5") (pintype "power_in"))
      (node (ref "G1") (pin "GND6") (pinfunction "GND6_GND6") (pintype "power_in"))
      (node (ref "G1") (pin "GND7") (pinfunction "GND7_GND7") (pintype "power_in"))
      (node (ref "G1") (pin "GND8") (pinfunction "GND8_GND8") (pintype "power_in"))
      (node (ref "IC1") (pin "2") (pinfunction "GNDSIG_2") (pintype "input"))
      (node (ref "IC1") (pin "3") (pinfunction "~{ON/OFF}_3") (pintype "input"))
      (node (ref "IC1") (pin "4") (pinfunction "GND_4") (pintype "power_in"))
      (node (ref "IC2") (pin "2") (pinfunction "VSS_2") (pintype "power_in"))
      (node (ref "J1") (pin "2") (pinfunction "2_2") (pintype "passive"))
      (node (ref "J1") (pin "3") (pinfunction "3_3") (pintype "passive"))
      (node (ref "JP1") (pin "4") (pinfunction "4_4") (pintype "passive"))
      (node (ref "JP10") (pin "5") (pinfunction "5_5") (pintype "passive"))
      (node (ref "JP2") (pin "8") (pinfunction "8_8") (pintype "passive"))
      (node (ref "JP3") (pin "5") (pinfunction "5_5") (pintype "passive"))
      (node (ref "JP3") (pin "6") (pinfunction "6_6") (pintype "passive"))
      (node (ref "JP4") (pin "5") (pinfunction "5_5") (pintype "passive"))
      (node (ref "JP4") (pin "6") (pinfunction "6_6") (pintype "passive"))
      (node (ref "JP5") (pin "5") (pinfunction "5_5") (pintype "passive"))
      (node (ref "JP5") (pin "6") (pinfunction "6_6") (pintype "passive"))
      (node (ref "JP6") (pin "5") (pinfunction "5_5") (pintype "passive"))
      (node (ref "JP6") (pin "6") (pinfunction "6_6") (pintype "passive"))
      (node (ref "JP8") (pin "5") (pinfunction "5_5") (pintype "passive"))
      (node (ref "JP9") (pin "5") (pinfunction "5_5") (pintype "passive"))
      (node (ref "Q1") (pin "2") (pinfunction "S_2") (pintype "passive"))
      (node (ref "Q10") (pin "2") (pinfunction "S_2") (pintype "passive"))
      (node (ref "Q11") (pin "2") (pinfunction "S_2") (pintype "passive"))
      (node (ref "Q12") (pin "2") (pinfunction "S_2") (pintype "passive"))
      (node (ref "Q13") (pin "2") (pinfunction "S_2") (pintype "passive"))
      (node (ref "Q14") (pin "2") (pinfunction "S_2") (pintype "passive"))
      (node (ref "Q15") (pin "2") (pinfunction "S_2") (pintype "passive"))
      (node (ref "Q16") (pin "2") (pinfunction "S_2") (pintype "passive"))
      (node (ref "Q2") (pin "2") (pinfunction "S_2") (pintype "passive"))
      (node (ref "Q3") (pin "2") (pinfunction "S_2") (pintype "passive"))
      (node (ref "Q4") (pin "2") (pinfunction "S_2") (pintype "passive"))
      (node (ref "Q5") (pin "2") (pinfunction "S_2") (pintype "passive"))
      (node (ref "Q6") (pin "2") (pinfunction "S_2") (pintype "passive"))
      (node (ref "Q7") (pin "2") (pinfunction "S_2") (pintype "passive"))
      (node (ref "Q8") (pin "2") (pinfunction "S_2") (pintype "passive"))
      (node (ref "Q9") (pin "2") (pinfunction "S_2") (pintype "passive"))
      (node (ref "R17") (pin "2") (pinfunction "2_2") (pintype "passive"))
      (node (ref "R50") (pin "1") (pinfunction "1_1") (pintype "passive"))
      (node (ref "SJ13") (pin "2") (pinfunction "2_2") (pintype "passive"))
      (node (ref "SJ14") (pin "P$2") (pinfunction "2_P$2") (pintype "passive"))
      (node (ref "SJ7") (pin "2") (pinfunction "2_2") (pintype "passive"))
      (node (ref "SJ8") (pin "P$2") (pinfunction "2_P$2") (pintype "passive"))
      (node (ref "U1") (pin "4") (pinfunction "SD_4") (pintype "bidirectional"))
      (node (ref "U1") (pin "5") (pinfunction "GND1_5") (pintype "power_in"))
      (node (ref "U1") (pin "6") (pinfunction "GND2_6") (pintype "power_in"))
      (node (ref "U1") (pin "7") (pinfunction "GND3_7") (pintype "power_in"))
      (node (ref "U1") (pin "8") (pinfunction "GND4_8") (pintype "power_in"))
      (node (ref "U10") (pin "3") (pinfunction "VSS_3") (pintype "power_in"))
      (node (ref "U11") (pin "13") (pinfunction "G_13") (pintype "input"))
      (node (ref "U11") (pin "8") (pinfunction "GND_8") (pintype "power_in"))
      (node (ref "U13") (pin "13") (pinfunction "G_13") (pintype "input"))
      (node (ref "U13") (pin "8") (pinfunction "GND_8") (pintype "power_in"))
      (node (ref "U2") (pin "2") (pinfunction "GND_2") (pintype "power_in"))
      (node (ref "U3") (pin "6") (pinfunction "INH_6") (pintype "input"))
      (node (ref "U3") (pin "8") (pinfunction "GND_8") (pintype "power_in"))
      (node (ref "U4") (pin "6") (pinfunction "INH_6") (pintype "input"))
      (node (ref "U4") (pin "8") (pinfunction "GND_8") (pintype "power_in"))
      (node (ref "U5") (pin "3") (pinfunction "VSS_3") (pintype "power_in"))
      (node (ref "U6") (pin "11") (pinfunction "V-_11") (pintype "power_in"))
      (node (ref "U7") (pin "3") (pinfunction "VSS_3") (pintype "power_in"))
      (node (ref "U8") (pin "3") (pinfunction "VSS_3") (pintype "power_in"))
      (node (ref "U9") (pin "11") (pinfunction "V-_11") (pintype "power_in"))
      (node (ref "X1") (pin "3") (pinfunction "3_3") (pintype "passive"))
      (node (ref "X1") (pin "6") (pinfunction "6_6") (pintype "passive"))
      (node (ref "X1") (pin "7") (pinfunction "7_7") (pintype "passive"))
      (node (ref "X2") (pin "3") (pinfunction "3_3") (pintype "passive"))
      (node (ref "X2") (pin "6") (pinfunction "6_6") (pintype "passive"))
      (node (ref "X2") (pin "7") (pinfunction "7_7") (pintype "passive"))
      (node (ref "X5") (pin "2") (pinfunction "2_2") (pintype "passive"))
    )
    (net (code "18") (name "I2CSCL") (class "Default")
      (node (ref "G1") (pin "PB6") (pinfunction "PB6_PB6") (pintype "bidirectional"))
      (node (ref "JP1") (pin "1") (pinfunction "1_1") (pintype "passive"))
      (node (ref "R2") (pin "2") (pinfunction "2_2") (pintype "passive"))
    )
    (net (code "19") (name "I2CSDA") (class "Default")
      (node (ref "G1") (pin "PB7") (pinfunction "PB7_PB7") (pintype "bidirectional"))
      (node (ref "JP1") (pin "2") (pinfunction "2_2") (pintype "passive"))
      (node (ref "R1") (pin "2") (pinfunction "2_2") (pintype "passive"))
    )
    (net (code "20") (name "ILAT") (class "Default")
      (node (ref "G1") (pin "PA6") (pinfunction "PA6_PA6") (pintype "bidirectional"))
      (node (ref "U3") (pin "15") (pinfunction "SH/~{LD}_15") (pintype "input"))
      (node (ref "U4") (pin "15") (pinfunction "SH/~{LD}_15") (pintype "input"))
    )
    (net (code "21") (name "MISO") (class "Default")
      (node (ref "G1") (pin "PB4") (pinfunction "PB4_PB4") (pintype "bidirectional"))
      (node (ref "JP2") (pin "1") (pinfunction "1_1") (pintype "passive"))
    )
    (net (code "22") (name "MISO2") (class "Default")
      (node (ref "G1") (pin "PC2") (pinfunction "PC2_PC2") (pintype "bidirectional"))
      (node (ref "SJ4") (pin "P$2") (pinfunction "2_P$2") (pintype "passive"))
      (node (ref "SJ6") (pin "P$2") (pinfunction "2_P$2") (pintype "passive"))
      (node (ref "U4") (pin "13") (pinfunction "QH_13") (pintype "output"))
    )
    (net (code "23") (name "MOSI") (class "Default")
      (node (ref "G1") (pin "PB5") (pinfunction "PB5_PB5") (pintype "bidirectional"))
      (node (ref "R12") (pin "1") (pinfunction "1_1") (pintype "passive"))
      (node (ref "SJ19") (pin "P$2") (pinfunction "2_P$2") (pintype "passive"))
      (node (ref "SJ2") (pin "1") (pinfunction "1_1") (pintype "passive"))
      (node (ref "U13") (pin "14") (pinfunction "SER_14") (pintype "input"))
    )
    (net (code "24") (name "Net-(D3-PadA)") (class "Default")
      (node (ref "D3") (pin "A") (pinfunction "A_A") (pintype "passive"))
      (node (ref "D4") (pin "A") (pinfunction "A_A") (pintype "passive"))
      (node (ref "JP7") (pin "4") (pinfunction "4_4") (pintype "passive"))
    )
    (net (code "25") (name "Net-(D3-PadC)") (class "Default")
      (node (ref "D3") (pin "C") (pinfunction "C_C") (pintype "passive"))
      (node (ref "D4") (pin "C") (pinfunction "C_C") (pintype "passive"))
      (node (ref "JP7") (pin "1") (pinfunction "1_1") (pintype "passive"))
    )
    (net (code "26") (name "Net-(IC1-OUT)") (class "Default")
      (node (ref "D1") (pin "C") (pinfunction "C_C") (pintype "passive"))
      (node (ref "D2") (pin "C") (pinfunction "C_C") (pintype "passive"))
      (node (ref "IC1") (pin "7") (pinfunction "OUT_7") (pintype "passive"))
      (node (ref "L1") (pin "2") (pinfunction "2_2") (pintype "passive"))
      (node (ref "U1") (pin "2") (pinfunction "VOUT_2") (pintype "bidirectional"))
    )
    (net (code "27") (name "Net-(IC2-RS)") (class "Default")
      (node (ref "IC2") (pin "8") (pinfunction "RS_8") (pintype "bidirectional"))
      (node (ref "R17") (pin "1") (pinfunction "1_1") (pintype "passive"))
      (node (ref "U2") (pin "8") (pinfunction "RS_8") (pintype "input"))
    )
    (net (code "28") (name "Net-(IC2-VREF)") (class "Default")
      (node (ref "IC2") (pin "5") (pinfunction "VREF_5") (pintype "bidirectional"))
      (node (ref "SJ5") (pin "P$2") (pinfunction "2_P$2") (pintype "passive"))
      (node (ref "U2") (pin "5") (pinfunction "VREF_5") (pintype "output"))
    )
    (net (code "29") (name "Net-(JP7-Pad3)") (class "Default")
      (node (ref "JP7") (pin "3") (pinfunction "3_3") (pintype "passive"))
      (node (ref "R16") (pin "1") (pinfunction "1_1") (pintype "passive"))
    )
    (net (code "30") (name "Net-(JP8-Pad1)") (class "Default")
      (node (ref "JP8") (pin "1") (pinfunction "1_1") (pintype "passive"))
      (node (ref "R18") (pin "2") (pinfunction "2_2") (pintype "passive"))
      (node (ref "R26") (pin "2") (pinfunction "2_2") (pintype "passive"))
      (node (ref "RN1") (pin "1") (pinfunction "1_1") (pintype "passive"))
      (node (ref "RN2") (pin "9") (pinfunction "9_9") (pintype "passive"))
      (node (ref "X3") (pin "1") (pinfunction "1_1") (pintype "passive"))
    )
    (net (code "31") (name "Net-(JP9-Pad1)") (class "Default")
      (node (ref "JP9") (pin "1") (pinfunction "1_1") (pintype "passive"))
      (node (ref "R34") (pin "2") (pinfunction "2_2") (pintype "passive"))
      (node (ref "R42") (pin "2") (pinfunction "2_2") (pintype "passive"))
      (node (ref "RN3") (pin "1") (pinfunction "1_1") (pintype "passive"))
      (node (ref "RN4") (pin "9") (pinfunction "9_9") (pintype "passive"))
      (node (ref "X4") (pin "1") (pinfunction "1_1") (pintype "passive"))
    )
    (net (code "32") (name "Net-(Q1-D)") (class "Default")
      (node (ref "Q1") (pin "3") (pinfunction "D_3") (pintype "passive"))
      (node (ref "U12") (pin "18") (pinfunction "O1_18") (pintype "open_collector"))
      (node (ref "X7") (pin "1") (pinfunction "1_1") (pintype "passive"))
    )
    (net (code "33") (name "Net-(Q1-G)") (class "Default")
      (node (ref "Q1") (pin "1") (pinfunction "G_1") (pintype "passive"))
      (node (ref "R52") (pin "2") (pinfunction "2_2") (pintype "passive"))
    )
    (net (code "34") (name "Net-(Q2-D)") (class "Default")
      (node (ref "Q2") (pin "3") (pinfunction "D_3") (pintype "passive"))
      (node (ref "U12") (pin "17") (pinfunction "O2_17") (pintype "open_collector"))
      (node (ref "X7") (pin "2") (pinfunction "2_2") (pintype "passive"))
    )
    (net (code "35") (name "Net-(Q2-G)") (class "Default")
      (node (ref "Q2") (pin "1") (pinfunction "G_1") (pintype "passive"))
      (node (ref "R53") (pin "2") (pinfunction "2_2") (pintype "passive"))
    )
    (net (code "36") (name "Net-(Q3-D)") (class "Default")
      (node (ref "Q3") (pin "3") (pinfunction "D_3") (pintype "passive"))
      (node (ref "U12") (pin "16") (pinfunction "O3_16") (pintype "open_collector"))
      (node (ref "X7") (pin "3") (pinfunction "3_3") (pintype "passive"))
    )
    (net (code "37") (name "Net-(Q3-G)") (class "Default")
      (node (ref "Q3") (pin "1") (pinfunction "G_1") (pintype "passive"))
      (node (ref "R54") (pin "2") (pinfunction "2_2") (pintype "passive"))
    )
    (net (code "38") (name "Net-(Q4-D)") (class "Default")
      (node (ref "Q4") (pin "3") (pinfunction "D_3") (pintype "passive"))
      (node (ref "U12") (pin "15") (pinfunction "O4_15") (pintype "open_collector"))
      (node (ref "X7") (pin "4") (pinfunction "4_4") (pintype "passive"))
    )
    (net (code "39") (name "Net-(Q4-G)") (class "Default")
      (node (ref "Q4") (pin "1") (pinfunction "G_1") (pintype "passive"))
      (node (ref "R55") (pin "2") (pinfunction "2_2") (pintype "passive"))
    )
    (net (code "40") (name "Net-(Q5-D)") (class "Default")
      (node (ref "Q5") (pin "3") (pinfunction "D_3") (pintype "passive"))
      (node (ref "U12") (pin "14") (pinfunction "O5_14") (pintype "open_collector"))
      (node (ref "X7") (pin "5") (pinfunction "5_5") (pintype "passive"))
    )
    (net (code "41") (name "Net-(Q5-G)") (class "Default")
      (node (ref "Q5") (pin "1") (pinfunction "G_1") (pintype "passive"))
      (node (ref "R56") (pin "2") (pinfunction "2_2") (pintype "passive"))
    )
    (net (code "42") (name "Net-(Q6-D)") (class "Default")
      (node (ref "Q6") (pin "3") (pinfunction "D_3") (pintype "passive"))
      (node (ref "U12") (pin "13") (pinfunction "O6_13") (pintype "open_collector"))
      (node (ref "X7") (pin "6") (pinfunction "6_6") (pintype "passive"))
    )
    (net (code "43") (name "Net-(Q6-G)") (class "Default")
      (node (ref "Q6") (pin "1") (pinfunction "G_1") (pintype "passive"))
      (node (ref "R57") (pin "2") (pinfunction "2_2") (pintype "passive"))
    )
    (net (code "44") (name "Net-(Q7-D)") (class "Default")
      (node (ref "Q7") (pin "3") (pinfunction "D_3") (pintype "passive"))
      (node (ref "U12") (pin "12") (pinfunction "O7_12") (pintype "open_collector"))
      (node (ref "X7") (pin "7") (pinfunction "7_7") (pintype "passive"))
    )
    (net (code "45") (name "Net-(Q7-G)") (class "Default")
      (node (ref "Q7") (pin "1") (pinfunction "G_1") (pintype "passive"))
      (node (ref "R58") (pin "2") (pinfunction "2_2") (pintype "passive"))
    )
    (net (code "46") (name "Net-(Q8-D)") (class "Default")
      (node (ref "Q8") (pin "3") (pinfunction "D_3") (pintype "passive"))
      (node (ref "U12") (pin "11") (pinfunction "O8_11") (pintype "open_collector"))
      (node (ref "X7") (pin "8") (pinfunction "8_8") (pintype "passive"))
    )
    (net (code "47") (name "Net-(Q8-G)") (class "Default")
      (node (ref "Q8") (pin "1") (pinfunction "G_1") (pintype "passive"))
      (node (ref "R59") (pin "2") (pinfunction "2_2") (pintype "passive"))
    )
    (net (code "48") (name "Net-(Q9-D)") (class "Default")
      (node (ref "Q9") (pin "3") (pinfunction "D_3") (pintype "passive"))
      (node (ref "U14") (pin "18") (pinfunction "O1_18") (pintype "open_collector"))
      (node (ref "X8") (pin "1") (pinfunction "1_1") (pintype "passive"))
    )
    (net (code "49") (name "Net-(Q9-G)") (class "Default")
      (node (ref "Q9") (pin "1") (pinfunction "G_1") (pintype "passive"))
      (node (ref "R60") (pin "2") (pinfunction "2_2") (pintype "passive"))
    )
    (net (code "50") (name "Net-(Q10-D)") (class "Default")
      (node (ref "Q10") (pin "3") (pinfunction "D_3") (pintype "passive"))
      (node (ref "U14") (pin "17") (pinfunction "O2_17") (pintype "open_collector"))
      (node (ref "X8") (pin "2") (pinfunction "2_2") (pintype "passive"))
    )
    (net (code "51") (name "Net-(Q10-G)") (class "Default")
      (node (ref "Q10") (pin "1") (pinfunction "G_1") (pintype "passive"))
      (node (ref "R61") (pin "2") (pinfunction "2_2") (pintype "passive"))
    )
    (net (code "52") (name "Net-(Q11-D)") (class "Default")
      (node (ref "Q11") (pin "3") (pinfunction "D_3") (pintype "passive"))
      (node (ref "U14") (pin "16") (pinfunction "O3_16") (pintype "open_collector"))
      (node (ref "X8") (pin "3") (pinfunction "3_3") (pintype "passive"))
    )
    (net (code "53") (name "Net-(Q11-G)") (class "Default")
      (node (ref "Q11") (pin "1") (pinfunction "G_1") (pintype "passive"))
      (node (ref "R62") (pin "2") (pinfunction "2_2") (pintype "passive"))
    )
    (net (code "54") (name "Net-(Q12-D)") (class "Default")
      (node (ref "Q12") (pin "3") (pinfunction "D_3") (pintype "passive"))
      (node (ref "U14") (pin "15") (pinfunction "O4_15") (pintype "open_collector"))
      (node (ref "X8") (pin "4") (pinfunction "4_4") (pintype "passive"))
    )
    (net (code "55") (name "Net-(Q12-G)") (class "Default")
      (node (ref "Q12") (pin "1") (pinfunction "G_1") (pintype "passive"))
      (node (ref "R63") (pin "2") (pinfunction "2_2") (pintype "passive"))
    )
    (net (code "56") (name "Net-(Q13-D)") (class "Default")
      (node (ref "Q13") (pin "3") (pinfunction "D_3") (pintype "passive"))
      (node (ref "U14") (pin "14") (pinfunction "O5_14") (pintype "open_collector"))
      (node (ref "X8") (pin "5") (pinfunction "5_5") (pintype "passive"))
    )
    (net (code "57") (name "Net-(Q13-G)") (class "Default")
      (node (ref "Q13") (pin "1") (pinfunction "G_1") (pintype "passive"))
      (node (ref "R64") (pin "2") (pinfunction "2_2") (pintype "passive"))
    )
    (net (code "58") (name "Net-(Q14-D)") (class "Default")
      (node (ref "Q14") (pin "3") (pinfunction "D_3") (pintype "passive"))
      (node (ref "U14") (pin "13") (pinfunction "O6_13") (pintype "open_collector"))
      (node (ref "X8") (pin "6") (pinfunction "6_6") (pintype "passive"))
    )
    (net (code "59") (name "Net-(Q14-G)") (class "Default")
      (node (ref "Q14") (pin "1") (pinfunction "G_1") (pintype "passive"))
      (node (ref "R65") (pin "2") (pinfunction "2_2") (pintype "passive"))
    )
    (net (code "60") (name "Net-(Q15-D)") (class "Default")
      (node (ref "Q15") (pin "3") (pinfunction "D_3") (pintype "passive"))
      (node (ref "U14") (pin "12") (pinfunction "O7_12") (pintype "open_collector"))
      (node (ref "X8") (pin "7") (pinfunction "7_7") (pintype "passive"))
    )
    (net (code "61") (name "Net-(Q15-G)") (class "Default")
      (node (ref "Q15") (pin "1") (pinfunction "G_1") (pintype "passive"))
      (node (ref "R66") (pin "2") (pinfunction "2_2") (pintype "passive"))
    )
    (net (code "62") (name "Net-(Q16-D)") (class "Default")
      (node (ref "Q16") (pin "3") (pinfunction "D_3") (pintype "passive"))
      (node (ref "U14") (pin "11") (pinfunction "O8_11") (pintype "open_collector"))
      (node (ref "X8") (pin "8") (pinfunction "8_8") (pintype "passive"))
    )
    (net (code "63") (name "Net-(Q16-G)") (class "Default")
      (node (ref "Q16") (pin "1") (pinfunction "G_1") (pintype "passive"))
      (node (ref "R67") (pin "2") (pinfunction "2_2") (pintype "passive"))
    )
    (net (code "64") (name "Net-(RN1A-2)") (class "Default")
      (node (ref "R26") (pin "1") (pinfunction "1_1") (pintype "passive"))
      (node (ref "RN1") (pin "16") (pinfunction "2_16") (pintype "passive"))
      (node (ref "U3") (pin "14") (pinfunction "H_14") (pintype "input"))
    )
    (net (code "65") (name "Net-(RN1B-1)") (class "Default")
      (node (ref "JP8") (pin "2") (pinfunction "2_2") (pintype "passive"))
      (node (ref "R19") (pin "2") (pinfunction "2_2") (pintype "passive"))
      (node (ref "R27") (pin "2") (pinfunction "2_2") (pintype "passive"))
      (node (ref "RN1") (pin "2") (pinfunction "1_2") (pintype "passive"))
      (node (ref "RN2") (pin "8") (pinfunction "8_8") (pintype "passive"))
      (node (ref "X3") (pin "2") (pinfunction "2_2") (pintype "passive"))
    )
    (net (code "66") (name "Net-(RN1B-2)") (class "Default")
      (node (ref "R27") (pin "1") (pinfunction "1_1") (pintype "passive"))
      (node (ref "RN1") (pin "15") (pinfunction "2_15") (pintype "passive"))
      (node (ref "U3") (pin "12") (pinfunction "G_12") (pintype "input"))
    )
    (net (code "67") (name "Net-(RN1C-1)") (class "Default")
      (node (ref "JP8") (pin "3") (pinfunction "3_3") (pintype "passive"))
      (node (ref "R20") (pin "2") (pinfunction "2_2") (pintype "passive"))
      (node (ref "R28") (pin "2") (pinfunction "2_2") (pintype "passive"))
      (node (ref "RN1") (pin "3") (pinfunction "1_3") (pintype "passive"))
      (node (ref "RN2") (pin "7") (pinfunction "7_7") (pintype "passive"))
      (node (ref "X3") (pin "3") (pinfunction "3_3") (pintype "passive"))
    )
    (net (code "68") (name "Net-(RN1C-2)") (class "Default")
      (node (ref "R28") (pin "1") (pinfunction "1_1") (pintype "passive"))
      (node (ref "RN1") (pin "14") (pinfunction "2_14") (pintype "passive"))
      (node (ref "U3") (pin "11") (pinfunction "F_11") (pintype "input"))
    )
    (net (code "69") (name "Net-(RN1D-1)") (class "Default")
      (node (ref "JP8") (pin "4") (pinfunction "4_4") (pintype "passive"))
      (node (ref "R21") (pin "2") (pinfunction "2_2") (pintype "passive"))
      (node (ref "R29") (pin "2") (pinfunction "2_2") (pintype "passive"))
      (node (ref "RN1") (pin "4") (pinfunction "1_4") (pintype "passive"))
      (node (ref "RN2") (pin "6") (pinfunction "6_6") (pintype "passive"))
      (node (ref "X3") (pin "4") (pinfunction "4_4") (pintype "passive"))
    )
    (net (code "70") (name "Net-(RN1D-2)") (class "Default")
      (node (ref "R29") (pin "1") (pinfunction "1_1") (pintype "passive"))
      (node (ref "RN1") (pin "13") (pinfunction "2_13") (pintype "passive"))
      (node (ref "U3") (pin "10") (pinfunction "E_10") (pintype "input"))
    )
    (net (code "71") (name "Net-(RN1E-1)") (class "Default")
      (node (ref "JP8") (pin "7") (pinfunction "7_7") (pintype "passive"))
      (node (ref "R22") (pin "2") (pinfunction "2_2") (pintype "passive"))
      (node (ref "R30") (pin "2") (pinfunction "2_2") (pintype "passive"))
      (node (ref "RN1") (pin "5") (pinfunction "1_5") (pintype "passive"))
      (node (ref "RN2") (pin "5") (pinfunction "5_5") (pintype "passive"))
      (node (ref "X3") (pin "5") (pinfunction "5_5") (pintype "passive"))
    )
    (net (code "72") (name "Net-(RN1E-2)") (class "Default")
      (node (ref "R30") (pin "1") (pinfunction "1_1") (pintype "passive"))
      (node (ref "RN1") (pin "12") (pinfunction "2_12") (pintype "passive"))
      (node (ref "U3") (pin "5") (pinfunction "D_5") (pintype "input"))
    )
    (net (code "73") (name "Net-(RN1F-1)") (class "Default")
      (node (ref "JP8") (pin "8") (pinfunction "8_8") (pintype "passive"))
      (node (ref "R23") (pin "2") (pinfunction "2_2") (pintype "passive"))
      (node (ref "R31") (pin "2") (pinfunction "2_2") (pintype "passive"))
      (node (ref "RN1") (pin "6") (pinfunction "1_6") (pintype "passive"))
      (node (ref "RN2") (pin "4") (pinfunction "4_4") (pintype "passive"))
      (node (ref "X3") (pin "6") (pinfunction "6_6") (pintype "passive"))
    )
    (net (code "74") (name "Net-(RN1F-2)") (class "Default")
      (node (ref "R31") (pin "1") (pinfunction "1_1") (pintype "passive"))
      (node (ref "RN1") (pin "11") (pinfunction "2_11") (pintype "passive"))
      (node (ref "U3") (pin "4") (pinfunction "C_4") (pintype "input"))
    )
    (net (code "75") (name "Net-(RN1G-1)") (class "Default")
      (node (ref "JP8") (pin "9") (pinfunction "9_9") (pintype "passive"))
      (node (ref "R24") (pin "2") (pinfunction "2_2") (pintype "passive"))
      (node (ref "R32") (pin "2") (pinfunction "2_2") (pintype "passive"))
      (node (ref "RN1") (pin "7") (pinfunction "1_7") (pintype "passive"))
      (node (ref "RN2") (pin "3") (pinfunction "3_3") (pintype "passive"))
      (node (ref "X3") (pin "7") (pinfunction "7_7") (pintype "passive"))
    )
    (net (code "76") (name "Net-(RN1G-2)") (class "Default")
      (node (ref "R32") (pin "1") (pinfunction "1_1") (pintype "passive"))
      (node (ref "RN1") (pin "10") (pinfunction "2_10") (pintype "passive"))
      (node (ref "U3") (pin "3") (pinfunction "B_3") (pintype "input"))
    )
    (net (code "77") (name "Net-(RN1H-1)") (class "Default")
      (node (ref "JP8") (pin "10") (pinfunction "10_10") (pintype "passive"))
      (node (ref "R25") (pin "2") (pinfunction "2_2") (pintype "passive"))
      (node (ref "R33") (pin "2") (pinfunction "2_2") (pintype "passive"))
      (node (ref "RN1") (pin "8") (pinfunction "1_8") (pintype "passive"))
      (node (ref "RN2") (pin "2") (pinfunction "2_2") (pintype "passive"))
      (node (ref "X3") (pin "8") (pinfunction "8_8") (pintype "passive"))
    )
    (net (code "78") (name "Net-(RN1H-2)") (class "Default")
      (node (ref "R33") (pin "1") (pinfunction "1_1") (pintype "passive"))
      (node (ref "RN1") (pin "9") (pinfunction "2_9") (pintype "passive"))
      (node (ref "U3") (pin "2") (pinfunction "A_2") (pintype "input"))
    )
    (net (code "79") (name "Net-(RN3A-2)") (class "Default")
      (node (ref "R42") (pin "1") (pinfunction "1_1") (pintype "passive"))
      (node (ref "RN3") (pin "16") (pinfunction "2_16") (pintype "passive"))
      (node (ref "U4") (pin "14") (pinfunction "H_14") (pintype "input"))
    )
    (net (code "80") (name "Net-(RN3B-1)") (class "Default")
      (node (ref "JP9") (pin "2") (pinfunction "2_2") (pintype "passive"))
      (node (ref "R35") (pin "2") (pinfunction "2_2") (pintype "passive"))
      (node (ref "R43") (pin "2") (pinfunction "2_2") (pintype "passive"))
      (node (ref "RN3") (pin "2") (pinfunction "1_2") (pintype "passive"))
      (node (ref "RN4") (pin "8") (pinfunction "8_8") (pintype "passive"))
      (node (ref "X4") (pin "2") (pinfunction "2_2") (pintype "passive"))
    )
    (net (code "81") (name "Net-(RN3B-2)") (class "Default")
      (node (ref "R43") (pin "1") (pinfunction "1_1") (pintype "passive"))
      (node (ref "RN3") (pin "15") (pinfunction "2_15") (pintype "passive"))
      (node (ref "U4") (pin "12") (pinfunction "G_12") (pintype "input"))
    )
    (net (code "82") (name "Net-(RN3C-1)") (class "Default")
      (node (ref "JP9") (pin "3") (pinfunction "3_3") (pintype "passive"))
      (node (ref "R36") (pin "2") (pinfunction "2_2") (pintype "passive"))
      (node (ref "R44") (pin "2") (pinfunction "2_2") (pintype "passive"))
      (node (ref "RN3") (pin "3") (pinfunction "1_3") (pintype "passive"))
      (node (ref "RN4") (pin "7") (pinfunction "7_7") (pintype "passive"))
      (node (ref "X4") (pin "3") (pinfunction "3_3") (pintype "passive"))
    )
    (net (code "83") (name "Net-(RN3C-2)") (class "Default")
      (node (ref "R44") (pin "1") (pinfunction "1_1") (pintype "passive"))
      (node (ref "RN3") (pin "14") (pinfunction "2_14") (pintype "passive"))
      (node (ref "U4") (pin "11") (pinfunction "F_11") (pintype "input"))
    )
    (net (code "84") (name "Net-(RN3D-1)") (class "Default")
      (node (ref "JP9") (pin "4") (pinfunction "4_4") (pintype "passive"))
      (node (ref "R37") (pin "2") (pinfunction "2_2") (pintype "passive"))
      (node (ref "R45") (pin "2") (pinfunction "2_2") (pintype "passive"))
      (node (ref "RN3") (pin "4") (pinfunction "1_4") (pintype "passive"))
      (node (ref "RN4") (pin "6") (pinfunction "6_6") (pintype "passive"))
      (node (ref "X4") (pin "4") (pinfunction "4_4") (pintype "passive"))
    )
    (net (code "85") (name "Net-(RN3D-2)") (class "Default")
      (node (ref "R45") (pin "1") (pinfunction "1_1") (pintype "passive"))
      (node (ref "RN3") (pin "13") (pinfunction "2_13") (pintype "passive"))
      (node (ref "U4") (pin "10") (pinfunction "E_10") (pintype "input"))
    )
    (net (code "86") (name "Net-(RN3E-1)") (class "Default")
      (node (ref "JP9") (pin "7") (pinfunction "7_7") (pintype "passive"))
      (node (ref "R38") (pin "2") (pinfunction "2_2") (pintype "passive"))
      (node (ref "R46") (pin "2") (pinfunction "2_2") (pintype "passive"))
      (node (ref "RN3") (pin "5") (pinfunction "1_5") (pintype "passive"))
      (node (ref "RN4") (pin "5") (pinfunction "5_5") (pintype "passive"))
      (node (ref "X4") (pin "5") (pinfunction "5_5") (pintype "passive"))
    )
    (net (code "87") (name "Net-(RN3E-2)") (class "Default")
      (node (ref "R46") (pin "1") (pinfunction "1_1") (pintype "passive"))
      (node (ref "RN3") (pin "12") (pinfunction "2_12") (pintype "passive"))
      (node (ref "U4") (pin "5") (pinfunction "D_5") (pintype "input"))
    )
    (net (code "88") (name "Net-(RN3F-1)") (class "Default")
      (node (ref "JP9") (pin "8") (pinfunction "8_8") (pintype "passive"))
      (node (ref "R39") (pin "2") (pinfunction "2_2") (pintype "passive"))
      (node (ref "R47") (pin "2") (pinfunction "2_2") (pintype "passive"))
      (node (ref "RN3") (pin "6") (pinfunction "1_6") (pintype "passive"))
      (node (ref "RN4") (pin "4") (pinfunction "4_4") (pintype "passive"))
      (node (ref "X4") (pin "6") (pinfunction "6_6") (pintype "passive"))
    )
    (net (code "89") (name "Net-(RN3F-2)") (class "Default")
      (node (ref "R47") (pin "1") (pinfunction "1_1") (pintype "passive"))
      (node (ref "RN3") (pin "11") (pinfunction "2_11") (pintype "passive"))
      (node (ref "U4") (pin "4") (pinfunction "C_4") (pintype "input"))
    )
    (net (code "90") (name "Net-(RN3G-1)") (class "Default")
      (node (ref "JP9") (pin "9") (pinfunction "9_9") (pintype "passive"))
      (node (ref "R40") (pin "2") (pinfunction "2_2") (pintype "passive"))
      (node (ref "R48") (pin "2") (pinfunction "2_2") (pintype "passive"))
      (node (ref "RN3") (pin "7") (pinfunction "1_7") (pintype "passive"))
      (node (ref "RN4") (pin "3") (pinfunction "3_3") (pintype "passive"))
      (node (ref "X4") (pin "7") (pinfunction "7_7") (pintype "passive"))
    )
    (net (code "91") (name "Net-(RN3G-2)") (class "Default")
      (node (ref "R48") (pin "1") (pinfunction "1_1") (pintype "passive"))
      (node (ref "RN3") (pin "10") (pinfunction "2_10") (pintype "passive"))
      (node (ref "U4") (pin "3") (pinfunction "B_3") (pintype "input"))
    )
    (net (code "92") (name "Net-(RN3H-1)") (class "Default")
      (node (ref "JP9") (pin "10") (pinfunction "10_10") (pintype "passive"))
      (node (ref "R41") (pin "2") (pinfunction "2_2") (pintype "passive"))
      (node (ref "R49") (pin "2") (pinfunction "2_2") (pintype "passive"))
      (node (ref "RN3") (pin "8") (pinfunction "1_8") (pintype "passive"))
      (node (ref "RN4") (pin "2") (pinfunction "2_2") (pintype "passive"))
      (node (ref "X4") (pin "8") (pinfunction "8_8") (pintype "passive"))
    )
    (net (code "93") (name "Net-(RN3H-2)") (class "Default")
      (node (ref "R49") (pin "1") (pinfunction "1_1") (pintype "passive"))
      (node (ref "RN3") (pin "9") (pinfunction "2_9") (pintype "passive"))
      (node (ref "U4") (pin "2") (pinfunction "A_2") (pintype "input"))
    )
    (net (code "94") (name "Net-(SJ1-2)") (class "Default")
      (node (ref "JP2") (pin "2") (pinfunction "2_2") (pintype "passive"))
      (node (ref "SJ1") (pin "P$2") (pinfunction "2_P$2") (pintype "passive"))
      (node (ref "SJ2") (pin "2") (pinfunction "2_2") (pintype "passive"))
    )
    (net (code "95") (name "Net-(SJ3-1)") (class "Default")
      (node (ref "G1") (pin "VIN2") (pinfunction "VIN2_VIN2") (pintype "power_in"))
      (node (ref "SJ3") (pin "P$1") (pinfunction "1_P$1") (pintype "passive"))
    )
    (net (code "96") (name "Net-(SJ4-1)") (class "Default")
      (node (ref "G1") (pin "PB14") (pinfunction "PB14_PB14") (pintype "bidirectional"))
      (node (ref "SJ4") (pin "P$1") (pinfunction "1_P$1") (pintype "passive"))
    )
    (net (code "97") (name "Net-(SJ10-1)") (class "Default")
      (node (ref "SJ10") (pin "P$1") (pinfunction "1_P$1") (pintype "passive"))
      (node (ref "SJ12") (pin "P$1") (pinfunction "1_P$1") (pintype "passive"))
      (node (ref "SJ8") (pin "P$1") (pinfunction "1_P$1") (pintype "passive"))
      (node (ref "U12") (pin "10") (pinfunction "CD+_10") (pintype "passive"))
    )
    (net (code "98") (name "Net-(SJ11-1)") (class "Default")
      (node (ref "SJ11") (pin "P$1") (pinfunction "1_P$1") (pintype "passive"))
      (node (ref "SJ7") (pin "1") (pinfunction "1_1") (pintype "passive"))
      (node (ref "SJ9") (pin "P$1") (pinfunction "1_P$1") (pintype "passive"))
      (node (ref "U12") (pin "9") (pinfunction "GND_9") (pintype "power_in"))
    )
    (net (code "99") (name "Net-(SJ14-1)") (class "Default")
      (node (ref "SJ14") (pin "P$1") (pinfunction "1_P$1") (pintype "passive"))
      (node (ref "SJ16") (pin "P$1") (pinfunction "1_P$1") (pintype "passive"))
      (node (ref "SJ18") (pin "P$1") (pinfunction "1_P$1") (pintype "passive"))
      (node (ref "U14") (pin "10") (pinfunction "CD+_10") (pintype "passive"))
    )
    (net (code "100") (name "Net-(SJ15-1)") (class "Default")
      (node (ref "SJ13") (pin "1") (pinfunction "1_1") (pintype "passive"))
      (node (ref "SJ15") (pin "P$1") (pinfunction "1_P$1") (pintype "passive"))
      (node (ref "SJ17") (pin "P$1") (pinfunction "1_P$1") (pintype "passive"))
      (node (ref "U14") (pin "9") (pinfunction "GND_9") (pintype "power_in"))
    )
    (net (code "101") (name "Net-(U5A-O)") (class "Default")
      (node (ref "JP10") (pin "10") (pinfunction "10_10") (pintype "passive"))
      (node (ref "U5") (pin "7") (pinfunction "O_7") (pintype "output"))
      (node (ref "U6") (pin "14") (pinfunction "OUT_14") (pintype "output"))
      (node (ref "X6") (pin "8") (pinfunction "8_8") (pintype "passive"))
    )
    (net (code "102") (name "Net-(U5B-O)") (class "Default")
      (node (ref "JP10") (pin "9") (pinfunction "9_9") (pintype "passive"))
      (node (ref "U5") (pin "5") (pinfunction "O_5") (pintype "output"))
      (node (ref "U6") (pin "1") (pinfunction "OUT_1") (pintype "output"))
      (node (ref "X6") (pin "7") (pinfunction "7_7") (pintype "passive"))
    )
    (net (code "103") (name "Net-(U6A--IN)") (class "Default")
      (node (ref "R50") (pin "2") (pinfunction "2_2") (pintype "passive"))
      (node (ref "R51") (pin "1") (pinfunction "1_1") (pintype "passive"))
      (node (ref "U6") (pin "13") (pinfunction "-IN_13") (pintype "input"))
      (node (ref "U6") (pin "2") (pinfunction "-IN_2") (pintype "input"))
      (node (ref "U6") (pin "6") (pinfunction "-IN_6") (pintype "input"))
      (node (ref "U6") (pin "9") (pinfunction "-IN_9") (pintype "input"))
      (node (ref "U9") (pin "13") (pinfunction "-IN_13") (pintype "input"))
      (node (ref "U9") (pin "2") (pinfunction "-IN_2") (pintype "input"))
      (node (ref "U9") (pin "6") (pinfunction "-IN_6") (pintype "input"))
      (node (ref "U9") (pin "9") (pinfunction "-IN_9") (pintype "input"))
    )
    (net (code "104") (name "Net-(U6B-OUT)") (class "Default")
      (node (ref "JP10") (pin "7") (pinfunction "7_7") (pintype "passive"))
      (node (ref "U6") (pin "7") (pinfunction "OUT_7") (pintype "output"))
      (node (ref "U7") (pin "7") (pinfunction "O_7") (pintype "output"))
      (node (ref "X6") (pin "5") (pinfunction "5_5") (pintype "passive"))
    )
    (net (code "105") (name "Net-(U6C-OUT)") (class "Default")
      (node (ref "JP10") (pin "8") (pinfunction "8_8") (pintype "passive"))
      (node (ref "U6") (pin "8") (pinfunction "OUT_8") (pintype "output"))
      (node (ref "U7") (pin "5") (pinfunction "O_5") (pintype "output"))
      (node (ref "X6") (pin "6") (pinfunction "6_6") (pintype "passive"))
    )
    (net (code "106") (name "Net-(U8A-O)") (class "Default")
      (node (ref "JP10") (pin "4") (pinfunction "4_4") (pintype "passive"))
      (node (ref "U8") (pin "7") (pinfunction "O_7") (pintype "output"))
      (node (ref "U9") (pin "14") (pinfunction "OUT_14") (pintype "output"))
      (node (ref "X6") (pin "4") (pinfunction "4_4") (pintype "passive"))
    )
    (net (code "107") (name "Net-(U8B-O)") (class "Default")
      (node (ref "JP10") (pin "3") (pinfunction "3_3") (pintype "passive"))
      (node (ref "U8") (pin "5") (pinfunction "O_5") (pintype "output"))
      (node (ref "U9") (pin "1") (pinfunction "OUT_1") (pintype "output"))
      (node (ref "X6") (pin "3") (pinfunction "3_3") (pintype "passive"))
    )
    (net (code "108") (name "Net-(U10A-O)") (class "Default")
      (node (ref "JP10") (pin "1") (pinfunction "1_1") (pintype "passive"))
      (node (ref "U10") (pin "7") (pinfunction "O_7") (pintype "output"))
      (node (ref "U9") (pin "7") (pinfunction "OUT_7") (pintype "output"))
      (node (ref "X6") (pin "1") (pinfunction "1_1") (pintype "passive"))
    )
    (net (code "109") (name "Net-(U10B-O)") (class "Default")
      (node (ref "JP10") (pin "2") (pinfunction "2_2") (pintype "passive"))
      (node (ref "U10") (pin "5") (pinfunction "O_5") (pintype "output"))
      (node (ref "U9") (pin "8") (pinfunction "OUT_8") (pintype "output"))
      (node (ref "X6") (pin "2") (pinfunction "2_2") (pintype "passive"))
    )
    (net (code "110") (name "Net-(U11A-QA)") (class "Default")
      (node (ref "R52") (pin "1") (pinfunction "1_1") (pintype "passive"))
      (node (ref "U11") (pin "15") (pinfunction "QA_15") (pintype "tri_state"))
      (node (ref "U12") (pin "1") (pinfunction "I1_1") (pintype "input"))
    )
    (net (code "111") (name "Net-(U11A-QB)") (class "Default")
      (node (ref "R53") (pin "1") (pinfunction "1_1") (pintype "passive"))
      (node (ref "U11") (pin "1") (pinfunction "QB_1") (pintype "tri_state"))
      (node (ref "U12") (pin "2") (pinfunction "I2_2") (pintype "input"))
    )
    (net (code "112") (name "Net-(U11A-QC)") (class "Default")
      (node (ref "R54") (pin "1") (pinfunction "1_1") (pintype "passive"))
      (node (ref "U11") (pin "2") (pinfunction "QC_2") (pintype "tri_state"))
      (node (ref "U12") (pin "3") (pinfunction "I3_3") (pintype "input"))
    )
    (net (code "113") (name "Net-(U11A-QD)") (class "Default")
      (node (ref "R55") (pin "1") (pinfunction "1_1") (pintype "passive"))
      (node (ref "U11") (pin "3") (pinfunction "QD_3") (pintype "tri_state"))
      (node (ref "U12") (pin "4") (pinfunction "I4_4") (pintype "input"))
    )
    (net (code "114") (name "Net-(U11A-QE)") (class "Default")
      (node (ref "R56") (pin "1") (pinfunction "1_1") (pintype "passive"))
      (node (ref "U11") (pin "4") (pinfunction "QE_4") (pintype "tri_state"))
      (node (ref "U12") (pin "5") (pinfunction "I5_5") (pintype "input"))
    )
    (net (code "115") (name "Net-(U11A-QF)") (class "Default")
      (node (ref "R57") (pin "1") (pinfunction "1_1") (pintype "passive"))
      (node (ref "U11") (pin "5") (pinfunction "QF_5") (pintype "tri_state"))
      (node (ref "U12") (pin "6") (pinfunction "I6_6") (pintype "input"))
    )
    (net (code "116") (name "Net-(U11A-QG)") (class "Default")
      (node (ref "R58") (pin "1") (pinfunction "1_1") (pintype "passive"))
      (node (ref "U11") (pin "6") (pinfunction "QG_6") (pintype "tri_state"))
      (node (ref "U12") (pin "7") (pinfunction "I7_7") (pintype "input"))
    )
    (net (code "117") (name "Net-(U11A-QH)") (class "Default")
      (node (ref "R59") (pin "1") (pinfunction "1_1") (pintype "passive"))
      (node (ref "U11") (pin "7") (pinfunction "QH_7") (pintype "tri_state"))
      (node (ref "U12") (pin "8") (pinfunction "I8_8") (pintype "input"))
    )
    (net (code "118") (name "Net-(U13A-QA)") (class "Default")
      (node (ref "R60") (pin "1") (pinfunction "1_1") (pintype "passive"))
      (node (ref "U13") (pin "15") (pinfunction "QA_15") (pintype "tri_state"))
      (node (ref "U14") (pin "1") (pinfunction "I1_1") (pintype "input"))
    )
    (net (code "119") (name "Net-(U13A-QB)") (class "Default")
      (node (ref "R61") (pin "1") (pinfunction "1_1") (pintype "passive"))
      (node (ref "U13") (pin "1") (pinfunction "QB_1") (pintype "tri_state"))
      (node (ref "U14") (pin "2") (pinfunction "I2_2") (pintype "input"))
    )
    (net (code "120") (name "Net-(U13A-QC)") (class "Default")
      (node (ref "R62") (pin "1") (pinfunction "1_1") (pintype "passive"))
      (node (ref "U13") (pin "2") (pinfunction "QC_2") (pintype "tri_state"))
      (node (ref "U14") (pin "3") (pinfunction "I3_3") (pintype "input"))
    )
    (net (code "121") (name "Net-(U13A-QD)") (class "Default")
      (node (ref "R63") (pin "1") (pinfunction "1_1") (pintype "passive"))
      (node (ref "U13") (pin "3") (pinfunction "QD_3") (pintype "tri_state"))
      (node (ref "U14") (pin "4") (pinfunction "I4_4") (pintype "input"))
    )
    (net (code "122") (name "Net-(U13A-QE)") (class "Default")
      (node (ref "R64") (pin "1") (pinfunction "1_1") (pintype "passive"))
      (node (ref "U13") (pin "4") (pinfunction "QE_4") (pintype "tri_state"))
      (node (ref "U14") (pin "5") (pinfunction "I5_5") (pintype "input"))
    )
    (net (code "123") (name "Net-(U13A-QF)") (class "Default")
      (node (ref "R65") (pin "1") (pinfunction "1_1") (pintype "passive"))
      (node (ref "U13") (pin "5") (pinfunction "QF_5") (pintype "tri_state"))
      (node (ref "U14") (pin "6") (pinfunction "I6_6") (pintype "input"))
    )
    (net (code "124") (name "Net-(U13A-QG)") (class "Default")
      (node (ref "R66") (pin "1") (pinfunction "1_1") (pintype "passive"))
      (node (ref "U13") (pin "6") (pinfunction "QG_6") (pintype "tri_state"))
      (node (ref "U14") (pin "7") (pinfunction "I7_7") (pintype "input"))
    )
    (net (code "125") (name "Net-(U13A-QH)") (class "Default")
      (node (ref "R67") (pin "1") (pinfunction "1_1") (pintype "passive"))
      (node (ref "U13") (pin "7") (pinfunction "QH_7") (pintype "tri_state"))
      (node (ref "U14") (pin "8") (pinfunction "I8_8") (pintype "input"))
    )
    (net (code "126") (name "Net-(X1-Pad4)") (class "Default")
      (node (ref "X1") (pin "4") (pinfunction "4_4") (pintype "passive"))
      (node (ref "X2") (pin "4") (pinfunction "4_4") (pintype "passive"))
    )
    (net (code "127") (name "Net-(X1-Pad5)") (class "Default")
      (node (ref "X1") (pin "5") (pinfunction "5_5") (pintype "passive"))
      (node (ref "X2") (pin "5") (pinfunction "5_5") (pintype "passive"))
    )
    (net (code "128") (name "OLAT") (class "Default")
      (node (ref "G1") (pin "PA8") (pinfunction "PA8_PA8") (pintype "bidirectional"))
      (node (ref "R11") (pin "1") (pinfunction "1_1") (pintype "passive"))
      (node (ref "U11") (pin "12") (pinfunction "RCK_12") (pintype "input"))
      (node (ref "U13") (pin "12") (pinfunction "RCK_12") (pintype "input"))
    )
    (net (code "129") (name "SCK") (class "Default")
      (node (ref "G1") (pin "PB3") (pinfunction "PB3_PB3") (pintype "bidirectional"))
      (node (ref "JP2") (pin "3") (pinfunction "3_3") (pintype "passive"))
      (node (ref "R13") (pin "1") (pinfunction "1_1") (pintype "passive"))
      (node (ref "U11") (pin "11") (pinfunction "SCK_11") (pintype "input"))
      (node (ref "U13") (pin "11") (pinfunction "SCK_11") (pintype "input"))
    )
    (net (code "130") (name "SCK2") (class "Default")
      (node (ref "G1") (pin "PB10") (pinfunction "PB10_PB10") (pintype "bidirectional"))
      (node (ref "U3") (pin "7") (pinfunction "CLK_7") (pintype "input"))
      (node (ref "U4") (pin "7") (pinfunction "CLK_7") (pintype "input"))
    )
    (net (code "131") (name "SLNK1") (class "Default")
      (node (ref "SJ19") (pin "P$1") (pinfunction "1_P$1") (pintype "passive"))
      (node (ref "U11") (pin "14") (pinfunction "SER_14") (pintype "input"))
      (node (ref "U13") (pin "9") (pinfunction "QH*_9") (pintype "tri_state"))
    )
    (net (code "132") (name "SLNK2") (class "Default")
      (node (ref "SJ1") (pin "P$1") (pinfunction "1_P$1") (pintype "passive"))
      (node (ref "U11") (pin "9") (pinfunction "QH*_9") (pintype "tri_state"))
    )
    (net (code "133") (name "SLNK3") (class "Default")
      (node (ref "SJ6") (pin "P$1") (pinfunction "1_P$1") (pintype "passive"))
      (node (ref "U3") (pin "13") (pinfunction "QH_13") (pintype "output"))
      (node (ref "U4") (pin "1") (pinfunction "SER_1") (pintype "input"))
    )
    (net (code "134") (name "SRV1") (class "Default")
      (node (ref "G1") (pin "PC9") (pinfunction "PC9_PC9") (pintype "bidirectional"))
      (node (ref "JP6") (pin "2") (pinfunction "2_2") (pintype "passive"))
      (node (ref "R10") (pin "2") (pinfunction "2_2") (pintype "passive"))
    )
    (net (code "135") (name "SRV2") (class "Default")
      (node (ref "G1") (pin "PC7") (pinfunction "PC7_PC7") (pintype "bidirectional"))
      (node (ref "JP6") (pin "1") (pinfunction "1_1") (pintype "passive"))
      (node (ref "R9") (pin "2") (pinfunction "2_2") (pintype "passive"))
    )
    (net (code "136") (name "SRV3") (class "Default")
      (node (ref "G1") (pin "PC8") (pinfunction "PC8_PC8") (pintype "bidirectional"))
      (node (ref "JP5") (pin "2") (pinfunction "2_2") (pintype "passive"))
      (node (ref "R8") (pin "2") (pinfunction "2_2") (pintype "passive"))
    )
    (net (code "137") (name "SRV4") (class "Default")
      (node (ref "G1") (pin "PC6") (pinfunction "PC6_PC6") (pintype "bidirectional"))
      (node (ref "JP5") (pin "1") (pinfunction "1_1") (pintype "passive"))
      (node (ref "R7") (pin "2") (pinfunction "2_2") (pintype "passive"))
    )
    (net (code "138") (name "SRV5") (class "Default")
      (node (ref "G1") (pin "PF1-PH1") (pinfunction "PF1-PH1_PF1-PH1") (pintype "bidirectional"))
      (node (ref "JP4") (pin "2") (pinfunction "2_2") (pintype "passive"))
      (node (ref "R6") (pin "2") (pinfunction "2_2") (pintype "passive"))
    )
    (net (code "139") (name "SRV6") (class "Default")
      (node (ref "G1") (pin "PA15") (pinfunction "PA15_PA15") (pintype "bidirectional"))
      (node (ref "JP4") (pin "1") (pinfunction "1_1") (pintype "passive"))
      (node (ref "R5") (pin "2") (pinfunction "2_2") (pintype "passive"))
    )
    (net (code "140") (name "SRV7") (class "Default")
      (node (ref "G1") (pin "PC12") (pinfunction "PC12_PC12") (pintype "bidirectional"))
      (node (ref "JP3") (pin "2") (pinfunction "2_2") (pintype "passive"))
      (node (ref "R4") (pin "2") (pinfunction "2_2") (pintype "passive"))
    )
    (net (code "141") (name "SRV8") (class "Default")
      (node (ref "G1") (pin "PD2") (pinfunction "PD2_PD2") (pintype "bidirectional"))
      (node (ref "JP3") (pin "1") (pinfunction "1_1") (pintype "passive"))
      (node (ref "R3") (pin "2") (pinfunction "2_2") (pintype "passive"))
    )
    (net (code "142") (name "TDRV1") (class "Default")
      (node (ref "G1") (pin "PB12") (pinfunction "PB12_PB12") (pintype "bidirectional"))
      (node (ref "U5") (pin "2") (pinfunction "I_2") (pintype "input"))
      (node (ref "U6") (pin "12") (pinfunction "+IN_12") (pintype "input"))
    )
    (net (code "143") (name "TDRV2") (class "Default")
      (node (ref "G1") (pin "PB2") (pinfunction "PB2_PB2") (pintype "bidirectional"))
      (node (ref "U5") (pin "4") (pinfunction "I_4") (pintype "input"))
      (node (ref "U6") (pin "3") (pinfunction "+IN_3") (pintype "input"))
    )
    (net (code "144") (name "TDRV3") (class "Default")
      (node (ref "G1") (pin "PB15") (pinfunction "PB15_PB15") (pintype "bidirectional"))
      (node (ref "U6") (pin "10") (pinfunction "+IN_10") (pintype "input"))
      (node (ref "U7") (pin "4") (pinfunction "I_4") (pintype "input"))
    )
    (net (code "145") (name "TDRV4") (class "Default")
      (node (ref "G1") (pin "PB1") (pinfunction "PB1_PB1") (pintype "bidirectional"))
      (node (ref "U6") (pin "5") (pinfunction "+IN_5") (pintype "input"))
      (node (ref "U7") (pin "2") (pinfunction "I_2") (pintype "input"))
    )
    (net (code "146") (name "TDRV5") (class "Default")
      (node (ref "G1") (pin "PA0") (pinfunction "PA0_PA0") (pintype "bidirectional"))
      (node (ref "U8") (pin "2") (pinfunction "I_2") (pintype "input"))
      (node (ref "U9") (pin "12") (pinfunction "+IN_12") (pintype "input"))
    )
    (net (code "147") (name "TDRV6") (class "Default")
      (node (ref "G1") (pin "PA4") (pinfunction "PA4_PA4") (pintype "bidirectional"))
      (node (ref "U8") (pin "4") (pinfunction "I_4") (pintype "input"))
      (node (ref "U9") (pin "3") (pinfunction "+IN_3") (pintype "input"))
    )
    (net (code "148") (name "TDRV7") (class "Default")
      (node (ref "G1") (pin "PC3") (pinfunction "PC3_PC3") (pintype "bidirectional"))
      (node (ref "U10") (pin "4") (pinfunction "I_4") (pintype "input"))
      (node (ref "U9") (pin "10") (pinfunction "+IN_10") (pintype "input"))
    )
    (net (code "149") (name "TDRV8") (class "Default")
      (node (ref "G1") (pin "PC0") (pinfunction "PC0_PC0") (pintype "bidirectional"))
      (node (ref "U10") (pin "2") (pinfunction "I_2") (pintype "input"))
      (node (ref "U9") (pin "5") (pinfunction "+IN_5") (pintype "input"))
    )
    (net (code "150") (name "V+") (class "Default")
      (node (ref "C3") (pin "+") (pinfunction "+_+") (pintype "passive"))
      (node (ref "C4") (pin "1") (pinfunction "1_1") (pintype "passive"))
      (node (ref "G1") (pin "E5V") (pinfunction "E5V_E5V") (pintype "power_in"))
      (node (ref "IC1") (pin "1") (pinfunction "FB_1") (pintype "input"))
      (node (ref "L1") (pin "1") (pinfunction "1_1") (pintype "passive"))
      (node (ref "U1") (pin "3") (pinfunction "FB_3") (pintype "bidirectional"))
    )
    (net (code "151") (name "unconnected-(G1-PadBOOT0)") (class "Default")
      (node (ref "G1") (pin "BOOT0") (pinfunction "BOOT0_BOOT0") (pintype "bidirectional"))
    )
    (net (code "152") (name "unconnected-(G1-PadIOREF2)") (class "Default")
      (node (ref "G1") (pin "IOREF2") (pinfunction "IOREF2_IOREF2") (pintype "input"))
    )
    (net (code "153") (name "unconnected-(G1-PadNC1-PF7)") (class "Default")
      (node (ref "G1") (pin "NC1-PF7") (pinfunction "NC1-PF7_NC1-PF7") (pintype "bidirectional"))
    )
    (net (code "154") (name "unconnected-(G1-PadNC2-PF6)") (class "Default")
      (node (ref "G1") (pin "NC2-PF6") (pinfunction "NC2-PF6_NC2-PF6") (pintype "bidirectional"))
    )
    (net (code "155") (name "unconnected-(G1-PadNC3)") (class "Default")
      (node (ref "G1") (pin "NC3") (pinfunction "NC3_NC3") (pintype "no_connect"))
    )
    (net (code "156") (name "unconnected-(G1-PadNC4)") (class "Default")
      (node (ref "G1") (pin "NC4") (pinfunction "NC4_NC4") (pintype "no_connect"))
    )
    (net (code "157") (name "unconnected-(G1-PadNC5-PD8)") (class "Default")
      (node (ref "G1") (pin "NC5-PD8") (pinfunction "NC5-PD8_NC5-PD8") (pintype "bidirectional"))
    )
    (net (code "158") (name "unconnected-(G1-PadNC6-PB11)") (class "Default")
      (node (ref "G1") (pin "NC6-PB11") (pinfunction "NC6-PB11_NC6-PB11") (pintype "no_connect"))
    )
    (net (code "159") (name "unconnected-(G1-PadNC7-PF5)") (class "Default")
      (node (ref "G1") (pin "NC7-PF5") (pinfunction "NC7-PF5_NC7-PF5") (pintype "bidirectional"))
    )
    (net (code "160") (name "unconnected-(G1-PadNC8-PF4)") (class "Default")
      (node (ref "G1") (pin "NC8-PF4") (pinfunction "NC8-PF4_NC8-PF4") (pintype "bidirectional"))
    )
    (net (code "161") (name "unconnected-(G1-PadNRESET)") (class "Default")
      (node (ref "G1") (pin "NRESET") (pinfunction "NRESET_NRESET") (pintype "input"))
    )
    (net (code "162") (name "unconnected-(G1-PadPA1)") (class "Default")
      (node (ref "G1") (pin "PA1") (pinfunction "PA1_PA1") (pintype "bidirectional"))
    )
    (net (code "163") (name "unconnected-(G1-PadPA2)") (class "Default")
      (node (ref "G1") (pin "PA2") (pinfunction "PA2_PA2") (pintype "bidirectional"))
    )
    (net (code "164") (name "unconnected-(G1-PadPA3)") (class "Default")
      (node (ref "G1") (pin "PA3") (pinfunction "PA3_PA3") (pintype "bidirectional"))
    )
    (net (code "165") (name "unconnected-(G1-PadPA5)") (class "Default")
      (node (ref "G1") (pin "PA5") (pinfunction "PA5_PA5") (pintype "bidirectional"))
    )
    (net (code "166") (name "unconnected-(G1-PadPA7)") (class "Default")
      (node (ref "G1") (pin "PA7") (pinfunction "PA7_PA7") (pintype "bidirectional"))
    )
    (net (code "167") (name "unconnected-(G1-PadPA9)") (class "Default")
      (node (ref "G1") (pin "PA9") (pinfunction "PA9_PA9") (pintype "bidirectional"))
    )
    (net (code "168") (name "unconnected-(G1-PadPA10)") (class "Default")
      (node (ref "G1") (pin "PA10") (pinfunction "PA10_PA10") (pintype "bidirectional"))
    )
    (net (code "169") (name "unconnected-(G1-PadPA11)") (class "Default")
      (node (ref "G1") (pin "PA11") (pinfunction "PA11_PA11") (pintype "bidirectional"))
    )
    (net (code "170") (name "unconnected-(G1-PadPA12)") (class "Default")
      (node (ref "G1") (pin "PA12") (pinfunction "PA12_PA12") (pintype "bidirectional"))
    )
    (net (code "171") (name "unconnected-(G1-PadPA13)") (class "Default")
      (node (ref "G1") (pin "PA13") (pinfunction "PA13_PA13") (pintype "bidirectional"))
    )
    (net (code "172") (name "unconnected-(G1-PadPA14)") (class "Default")
      (node (ref "G1") (pin "PA14") (pinfunction "PA14_PA14") (pintype "bidirectional"))
    )
    (net (code "173") (name "unconnected-(G1-PadPB0)") (class "Default")
      (node (ref "G1") (pin "PB0") (pinfunction "PB0_PB0") (pintype "bidirectional"))
    )
    (net (code "174") (name "unconnected-(G1-PadPB13)") (class "Default")
      (node (ref "G1") (pin "PB13") (pinfunction "PB13_PB13") (pintype "bidirectional"))
    )
    (net (code "175") (name "unconnected-(G1-PadPC1)") (class "Default")
      (node (ref "G1") (pin "PC1") (pinfunction "PC1_PC1") (pintype "bidirectional"))
    )
    (net (code "176") (name "unconnected-(G1-PadPC4)") (class "Default")
      (node (ref "G1") (pin "PC4") (pinfunction "PC4_PC4") (pintype "bidirectional"))
    )
    (net (code "177") (name "unconnected-(G1-PadPC5)") (class "Default")
      (node (ref "G1") (pin "PC5") (pinfunction "PC5_PC5") (pintype "bidirectional"))
    )
    (net (code "178") (name "unconnected-(G1-PadPC13)") (class "Default")
      (node (ref "G1") (pin "PC13") (pinfunction "PC13_PC13") (pintype "bidirectional"))
    )
    (net (code "179") (name "unconnected-(G1-PadPC14)") (class "Default")
      (node (ref "G1") (pin "PC14") (pinfunction "PC14_PC14") (pintype "bidirectional"))
    )
    (net (code "180") (name "unconnected-(G1-PadPC15)") (class "Default")
      (node (ref "G1") (pin "PC15") (pinfunction "PC15_PC15") (pintype "bidirectional"))
    )
    (net (code "181") (name "unconnected-(G1-PadPF0-PH0)") (class "Default")
      (node (ref "G1") (pin "PF0-PH0") (pinfunction "PF0-PH0_PF0-PH0") (pintype "bidirectional"))
    )
    (net (code "182") (name "unconnected-(H1-MOUNT-PadB3,3)") (class "Default")
      (node (ref "H1") (pin "B3,3") (pinfunction "MOUNT_B3,3") (pintype "passive"))
    )
    (net (code "183") (name "unconnected-(H2-MOUNT-PadB3,3)") (class "Default")
      (node (ref "H2") (pin "B3,3") (pinfunction "MOUNT_B3,3") (pintype "passive"))
    )
    (net (code "184") (name "unconnected-(H3-MOUNT-PadB3,3)") (class "Default")
      (node (ref "H3") (pin "B3,3") (pinfunction "MOUNT_B3,3") (pintype "passive"))
    )
    (net (code "185") (name "unconnected-(H4-MOUNT-PadB3,3)") (class "Default")
      (node (ref "H4") (pin "B3,3") (pinfunction "MOUNT_B3,3") (pintype "passive"))
    )
  )
)
